# SCH_Amiga-KickSmash-32-in-system-flash_2.net
KiCad netlist of a schematic drawn in EasyEDA
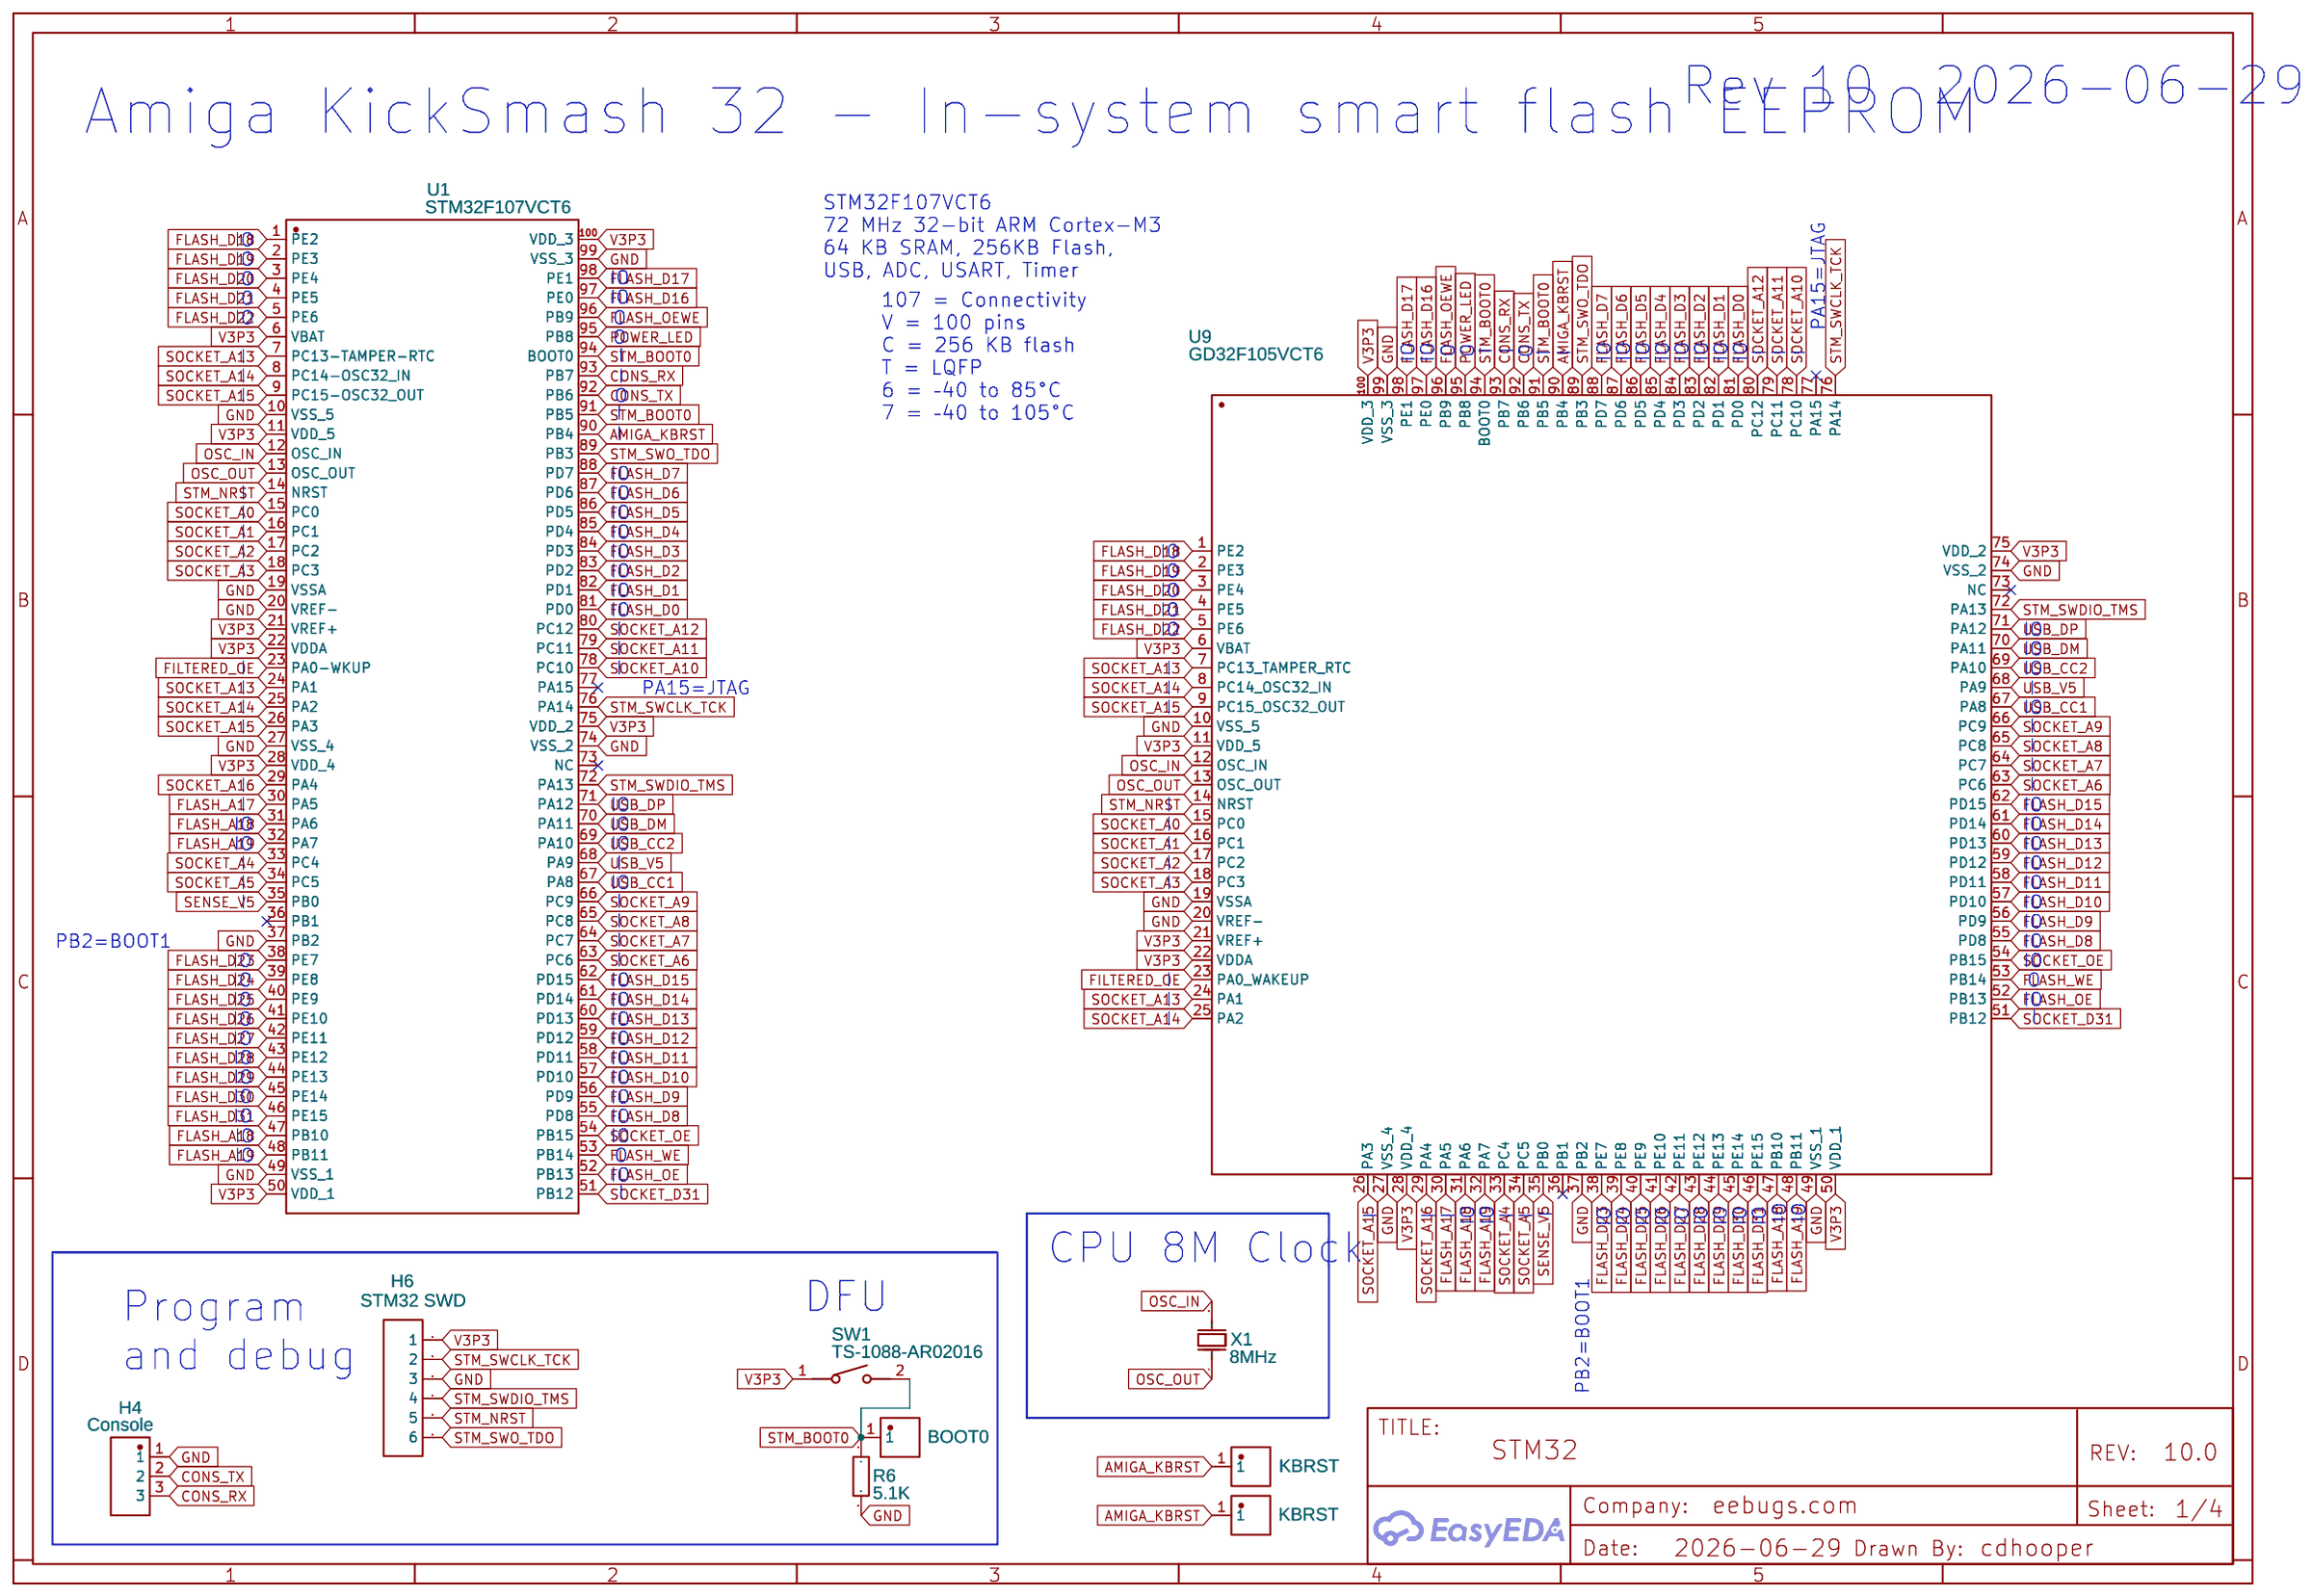
[diagram p0: CPU]
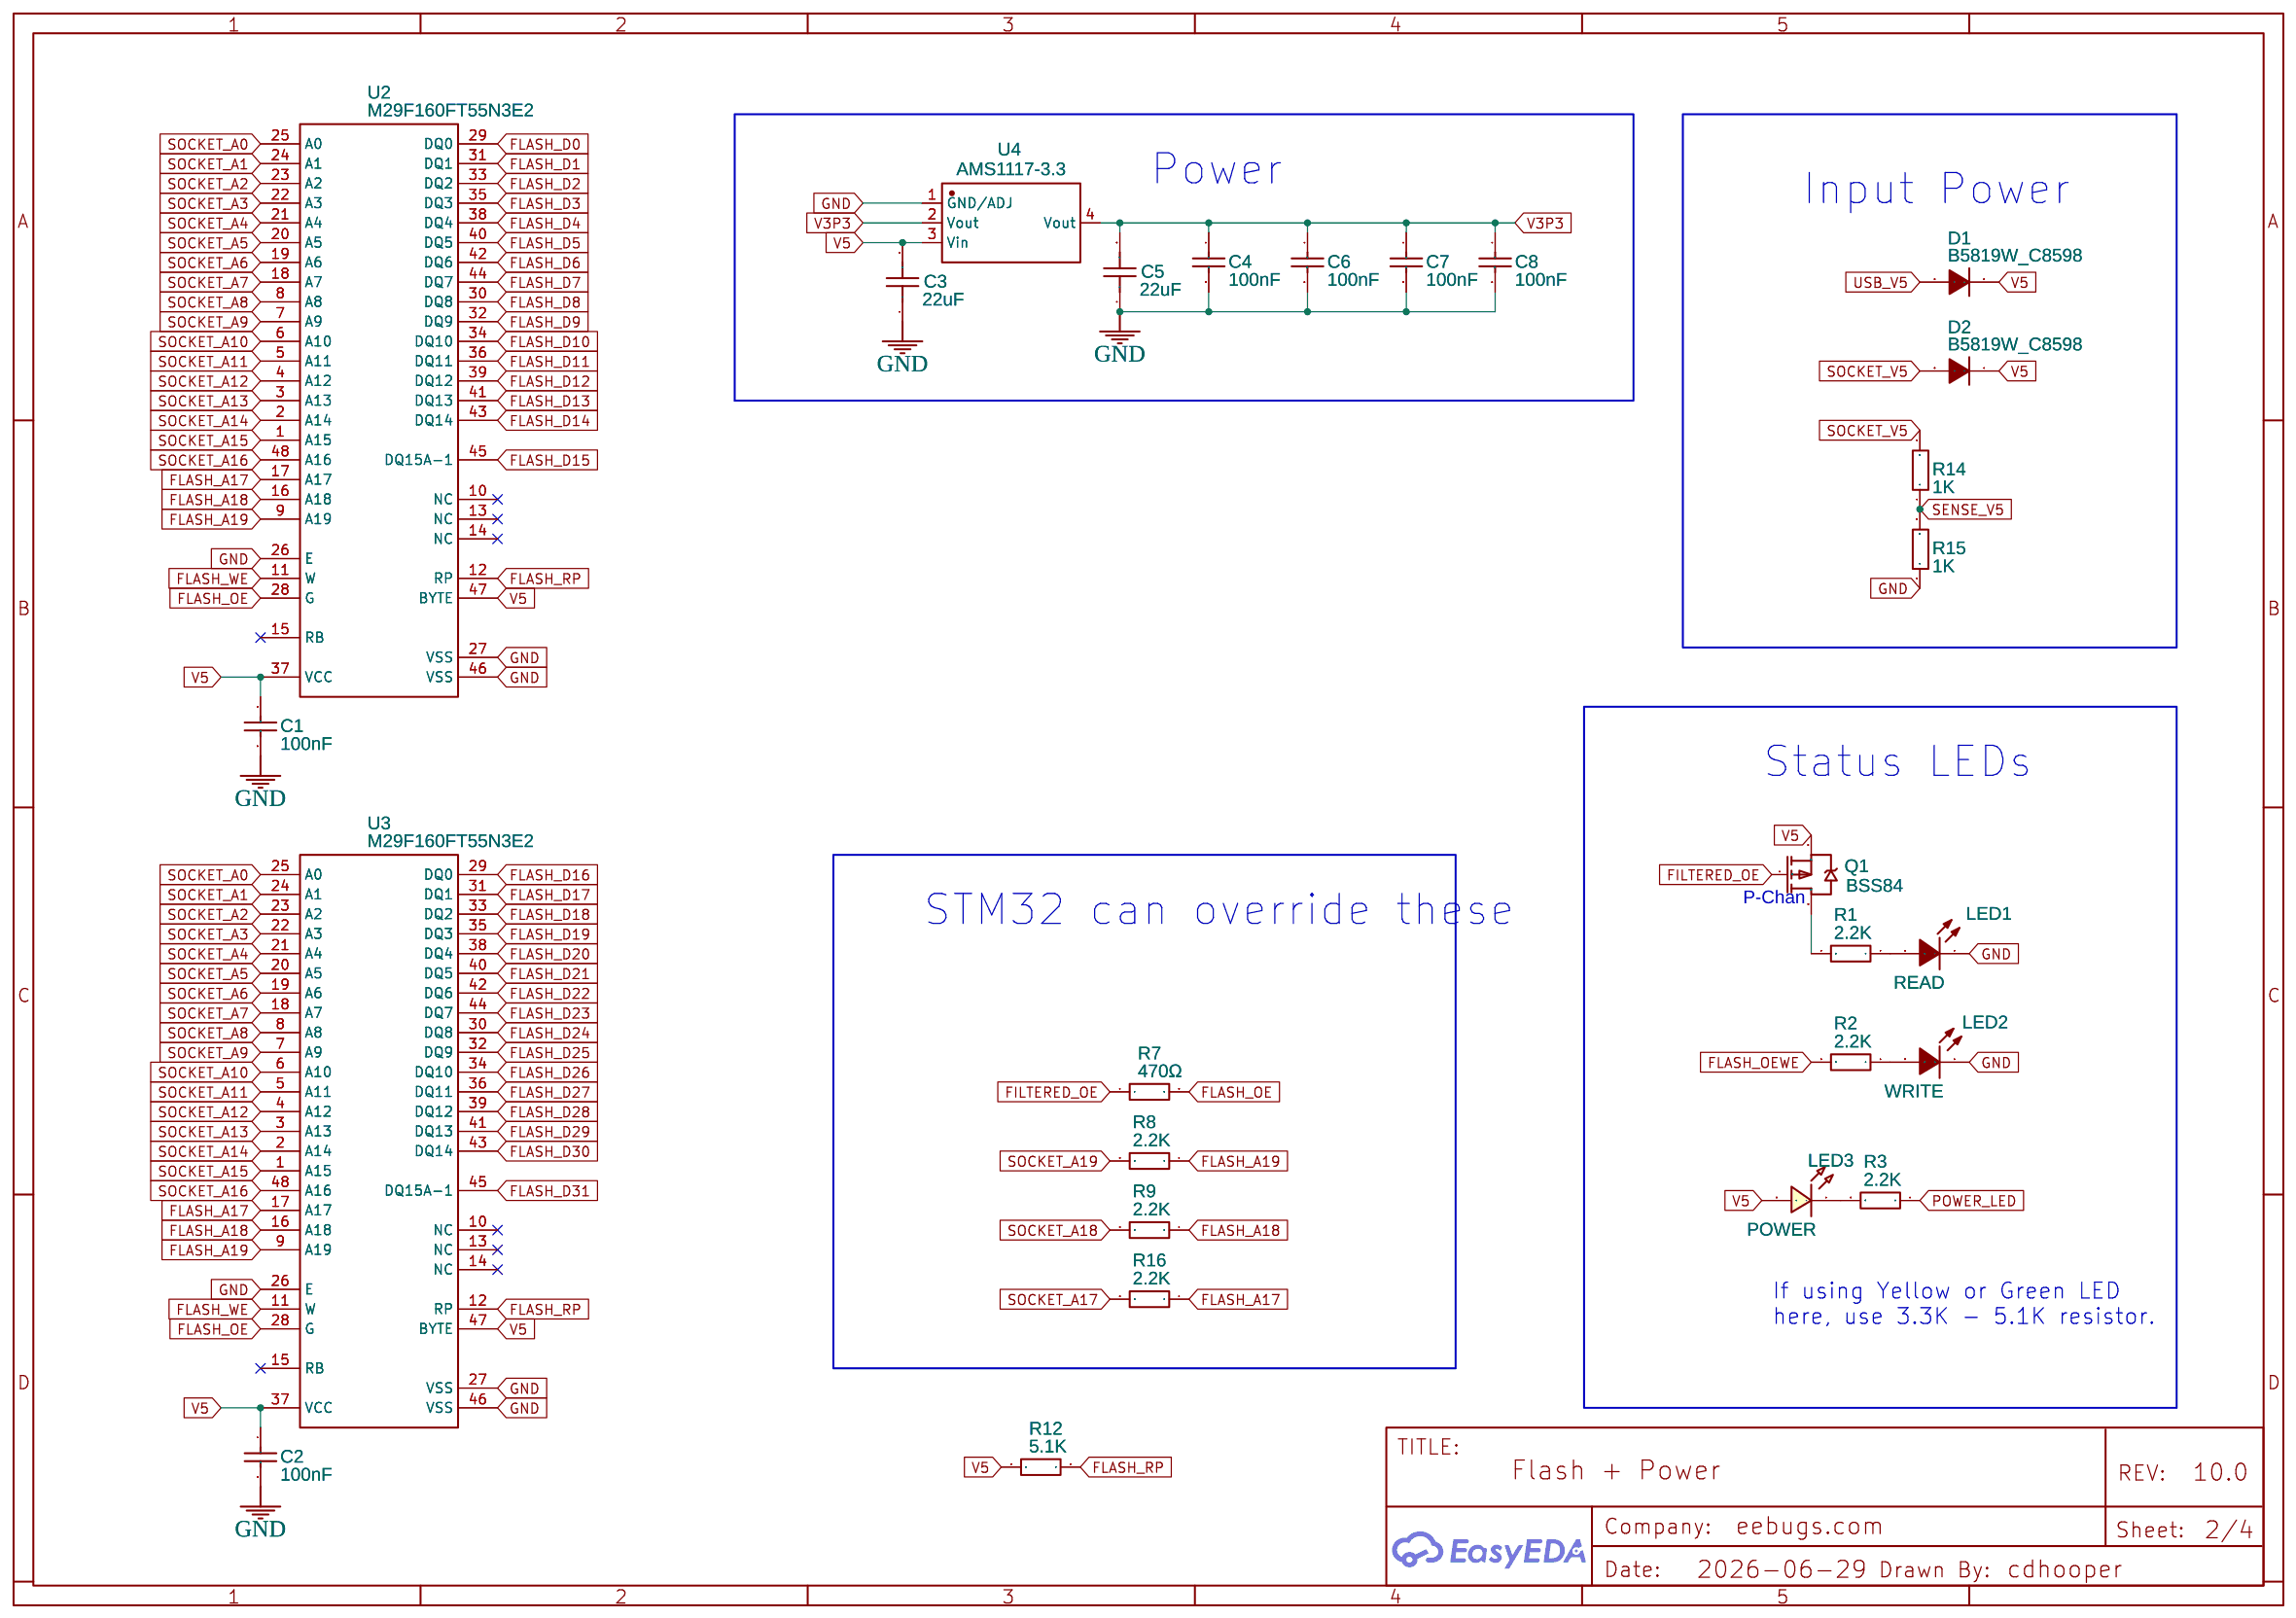
[diagram p1: Flash+PWR]
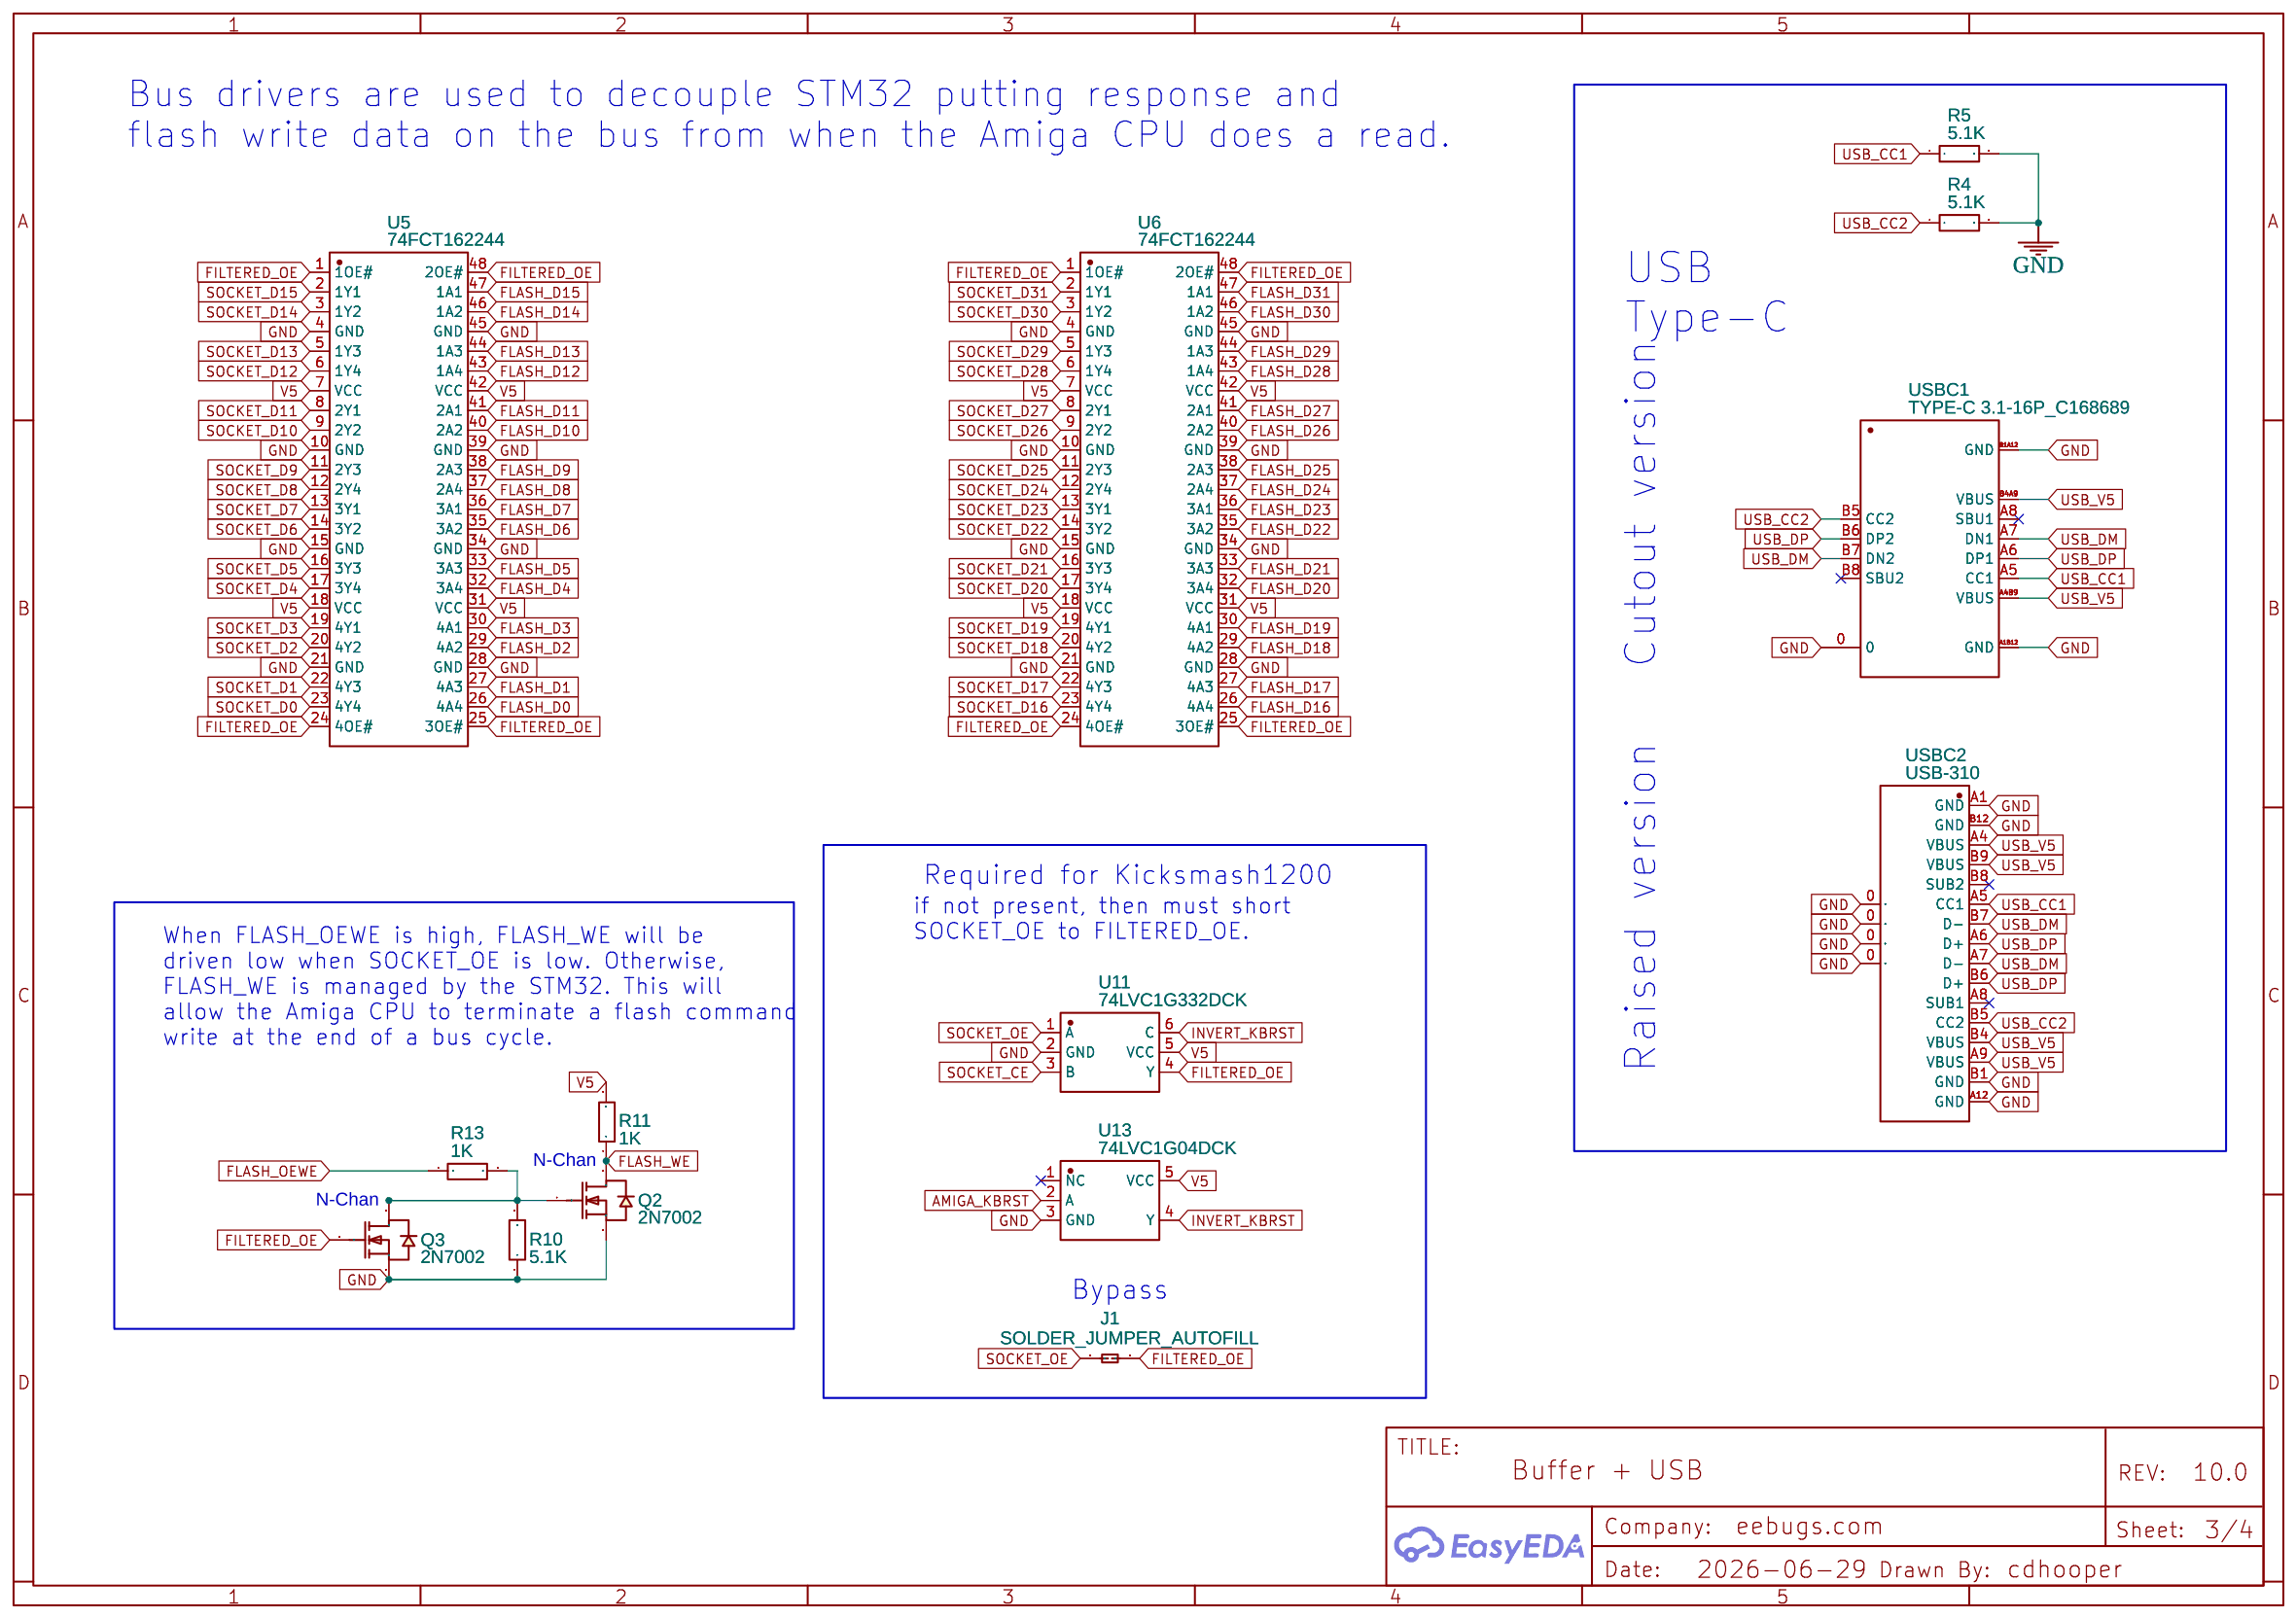
[diagram p2: Buffer+USB]
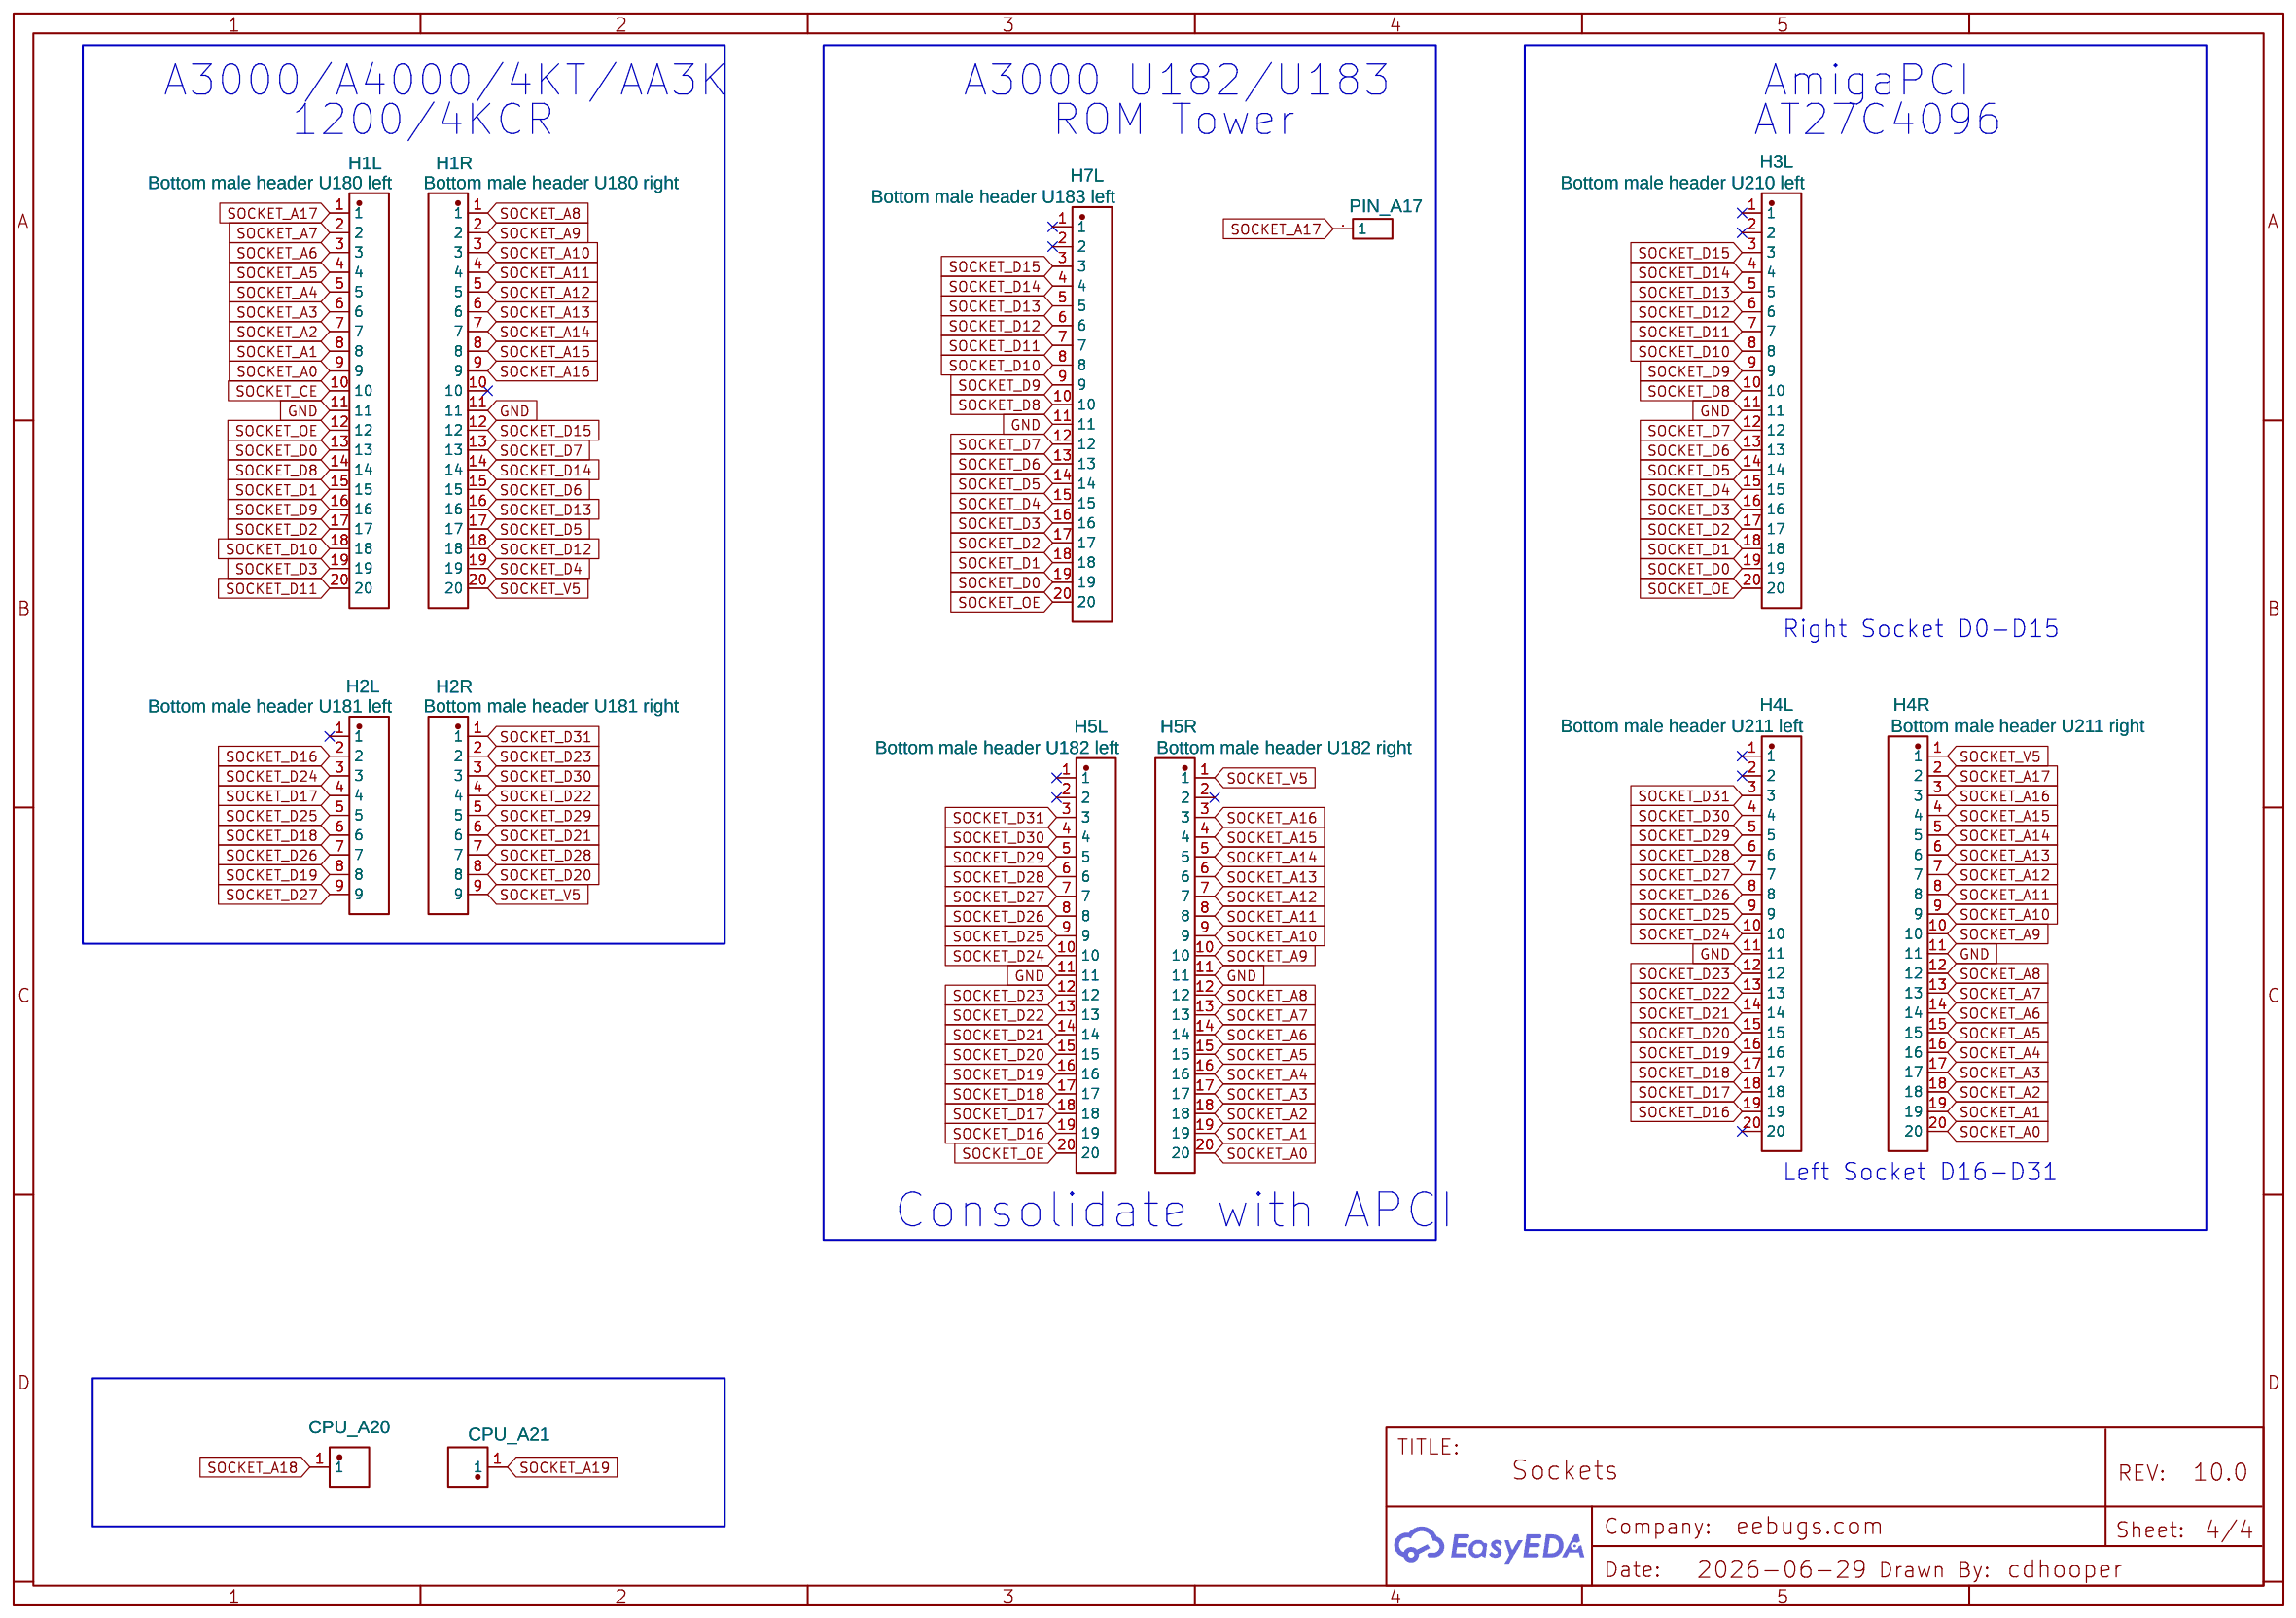
[diagram p3: Sockets]

(export (version "E")
  (design (tool "Eeschema 10.0.6"))
  (components
    (comp (ref "H1")
      (value "KBRST")
      (fields (field (name "Manufacturer Part") "MTAD1-D011196") (field (name "Manufacturer") "MINTRON(明硕)"))
      (libsource (lib "") (part "MTAD1-D011196"))
    )
    (comp (ref "H3")
      (value "KBRST")
      (fields
        (field (name "Manufacturer Part") "X6511WR-01H-C60D30R2")
        (field (name "Manufacturer") "XKB Connection(中国星坤)")
      )
      (libsource (lib "") (part "X6511WR-01H-C30D60R2"))
    )
    (comp (ref "H4")
      (value "Console")
      (fields (field (name "Manufacturer Part") "PZ254R-11-03P") (field (name "Manufacturer") "XFCN(兴飞)"))
      (libsource (lib "") (part "PZ254R-11-03P"))
    )
    (comp (ref "H5")
      (value "BOOT0")
      (fields
        (field (name "Manufacturer Part") "X6511WR-01H-C60D30R2")
        (field (name "Manufacturer") "XKB Connection(中国星坤)")
      )
      (libsource (lib "") (part "X6511WR-01H-C30D60R2"))
    )
    (comp (ref "H6")
      (value "STM32 SWD")
      (fields
        (field (name "Manufacturer Part") "2.54-1*6P反弯排针")
        (field (name "Manufacturer") "BOOMELE(博穆精密)")
      )
      (libsource (lib "") (part "Unknown_205_-100"))
    )
    (comp (ref "R6")
      (value "5.1K")
      (fields (field (name "Manufacturer Part") "0805W8F5101T5E") (field (name "Manufacturer") "UniOhm"))
      (libsource (lib "") (part "0805W8F5101T5E"))
    )
    (comp (ref "SW1")
      (value "TS-1088-AR02016")
      (fields (field (name "Manufacturer") "XUNPU(讯普)"))
      (libsource (lib "") (part "TS-1088-AR02016"))
    )
    (comp (ref "U1")
      (value "STM32F107VCT6")
      (fields (field (name "Manufacturer") "STMicroelectronics"))
      (libsource (lib "") (part "STM32F107VCT6"))
    )
    (comp (ref "U9")
      (value "GD32F105VCT6")
      (fields (field (name "Manufacturer") "GigaDevice(兆易创新)"))
      (libsource (lib "") (part "GD32F105VCT6"))
    )
    (comp (ref "X1")
      (value "8MHz")
      (fields (field (name "Manufacturer Part") "X50328MSB2GI") (field (name "Manufacturer") "YXC"))
      (libsource (lib "") (part "X50328MSB2GI"))
    )
    (comp (ref "C1")
      (value "100nF")
      (fields (field (name "Manufacturer Part") "CC0805KRX7R9BB104") (field (name "Manufacturer") "YAGEO"))
      (libsource (lib "") (part "CC0805KRX7R9BB104"))
    )
    (comp (ref "C2")
      (value "100nF")
      (fields (field (name "Manufacturer Part") "CC0805KRX7R9BB104") (field (name "Manufacturer") "YAGEO"))
      (libsource (lib "") (part "CC0805KRX7R9BB104"))
    )
    (comp (ref "C3")
      (value "22uF")
      (fields (field (name "Manufacturer Part") "CL21A226MAQNNNE") (field (name "Manufacturer") "SAMSUNG"))
      (libsource (lib "") (part "CL21A226MAQNNNE"))
    )
    (comp (ref "C4")
      (value "100nF")
      (fields (field (name "Manufacturer Part") "CC0805KRX7R9BB104") (field (name "Manufacturer") "YAGEO"))
      (libsource (lib "") (part "CC0805KRX7R9BB104"))
    )
    (comp (ref "C5")
      (value "22uF")
      (fields (field (name "Manufacturer Part") "CL21A226MAQNNNE") (field (name "Manufacturer") "SAMSUNG"))
      (libsource (lib "") (part "CL21A226MAQNNNE"))
    )
    (comp (ref "C6")
      (value "100nF")
      (fields (field (name "Manufacturer Part") "CC0805KRX7R9BB104") (field (name "Manufacturer") "YAGEO"))
      (libsource (lib "") (part "CC0805KRX7R9BB104"))
    )
    (comp (ref "C7")
      (value "100nF")
      (fields (field (name "Manufacturer Part") "CC0805KRX7R9BB104") (field (name "Manufacturer") "YAGEO"))
      (libsource (lib "") (part "CC0805KRX7R9BB104"))
    )
    (comp (ref "C8")
      (value "100nF")
      (fields (field (name "Manufacturer Part") "CC0805KRX7R9BB104") (field (name "Manufacturer") "YAGEO"))
      (libsource (lib "") (part "CC0805KRX7R9BB104"))
    )
    (comp (ref "D1")
      (value "B5819W_C8598")
      (fields (field (name "Manufacturer Part") "B5819W") (field (name "Manufacturer") "CJ"))
      (libsource (lib "") (part "B5819W_C8598"))
    )
    (comp (ref "D2")
      (value "B5819W_C8598")
      (fields (field (name "Manufacturer Part") "B5819W") (field (name "Manufacturer") "CJ"))
      (libsource (lib "") (part "B5819W_C8598"))
    )
    (comp (ref "LED1")
      (value "READ")
      (fields (field (name "Manufacturer Part") "17-21SUYC/TR8") (field (name "Manufacturer") "KENTO"))
      (libsource (lib "") (part "17-21SUYC/TR8"))
    )
    (comp (ref "LED2")
      (value "WRITE")
      (fields (field (name "Manufacturer Part") "0805G (Green)") (field (name "Manufacturer") "KENTO"))
      (libsource (lib "") (part "0805G (Green)"))
    )
    (comp (ref "LED3")
      (value "POWER")
      (fields
        (field (name "Manufacturer Part") "P2-0805UVTCS2-0.8T")
        (field (name "Manufacturer") "TUOZHAN(拓展光电)")
      )
      (libsource (lib "") (part "P2-0805UVTCS2-0.8T"))
    )
    (comp (ref "Q1")
      (value "BSS84")
      (fields (field (name "Manufacturer Part") "LBSS84LT1G") (field (name "Manufacturer") "LRC"))
      (libsource (lib "") (part "Unknown_905_-370"))
    )
    (comp (ref "R1")
      (value "2.2K")
      (fields (field (name "Manufacturer Part") "0805W8F2201T5E") (field (name "Manufacturer") "UniOhm"))
      (libsource (lib "") (part "0805W8F2201T5E"))
    )
    (comp (ref "R2")
      (value "2.2K")
      (fields (field (name "Manufacturer Part") "0805W8F2201T5E") (field (name "Manufacturer") "UniOhm"))
      (libsource (lib "") (part "0805W8F2201T5E"))
    )
    (comp (ref "R3")
      (value "2.2K")
      (fields (field (name "Manufacturer Part") "0805W8F2201T5E") (field (name "Manufacturer") "UniOhm"))
      (libsource (lib "") (part "0805W8F2201T5E"))
    )
    (comp (ref "R7")
      (value "470Ω")
      (fields
        (field (name "Manufacturer Part") "0805W8F4700T5E")
        (field (name "Manufacturer") "UNI-ROYAL(厚声)")
      )
      (libsource (lib "") (part "0805W8F4700T5E"))
    )
    (comp (ref "R8")
      (value "2.2K")
      (fields (field (name "Manufacturer Part") "0805W8F2201T5E") (field (name "Manufacturer") "UniOhm"))
      (libsource (lib "") (part "0805W8F2201T5E"))
    )
    (comp (ref "R9")
      (value "2.2K")
      (fields (field (name "Manufacturer Part") "0805W8F2201T5E") (field (name "Manufacturer") "UniOhm"))
      (libsource (lib "") (part "0805W8F2201T5E"))
    )
    (comp (ref "R12")
      (value "5.1K")
      (fields (field (name "Manufacturer Part") "0805W8F5101T5E") (field (name "Manufacturer") "UniOhm"))
      (libsource (lib "") (part "0805W8F5101T5E"))
    )
    (comp (ref "R14")
      (value "1K")
      (fields (field (name "Manufacturer Part") "0805W8F1001T5E") (field (name "Manufacturer") "UniOhm"))
      (libsource (lib "") (part "0805W8F1001T5E"))
    )
    (comp (ref "R15")
      (value "1K")
      (fields (field (name "Manufacturer Part") "0805W8F1001T5E") (field (name "Manufacturer") "UniOhm"))
      (libsource (lib "") (part "0805W8F1001T5E"))
    )
    (comp (ref "R16")
      (value "2.2K")
      (fields (field (name "Manufacturer Part") "0805W8F2201T5E") (field (name "Manufacturer") "UniOhm"))
      (libsource (lib "") (part "0805W8F2201T5E"))
    )
    (comp (ref "U2") (value "M29F160FT55N3E2") (libsource (lib "") (part "M29F160FT55N3E2")))
    (comp (ref "U3") (value "M29F160FT55N3E2") (libsource (lib "") (part "M29F160FT55N3E2")))
    (comp (ref "U4")
      (value "AMS1117-3.3")
      (fields (field (name "Manufacturer") "AMS"))
      (libsource (lib "") (part "AMS1117-3.3"))
    )
    (comp (ref "J1") (value "SOLDER_JUMPER_AUTOFILL") (libsource (lib "") (part "JUMPER_SOLDER_AUTOFILL")))
    (comp (ref "Q2")
      (value "2N7002")
      (fields (field (name "Manufacturer") "CJ(江苏长电/长晶)"))
      (libsource (lib "") (part "AO3400A"))
    )
    (comp (ref "Q3")
      (value "2N7002")
      (fields (field (name "Manufacturer") "CJ(江苏长电/长晶)"))
      (libsource (lib "") (part "AO3400A"))
    )
    (comp (ref "R4")
      (value "5.1K")
      (fields (field (name "Manufacturer Part") "0805W8F5101T5E") (field (name "Manufacturer") "UniOhm"))
      (libsource (lib "") (part "0805W8F5101T5E"))
    )
    (comp (ref "R5")
      (value "5.1K")
      (fields (field (name "Manufacturer Part") "0805W8F5101T5E") (field (name "Manufacturer") "UniOhm"))
      (libsource (lib "") (part "0805W8F5101T5E"))
    )
    (comp (ref "R10")
      (value "5.1K")
      (fields (field (name "Manufacturer Part") "0805W8F5101T5E") (field (name "Manufacturer") "UniOhm"))
      (libsource (lib "") (part "0805W8F5101T5E_1"))
    )
    (comp (ref "R11")
      (value "1K")
      (fields (field (name "Manufacturer Part") "0805W8F1001T5E") (field (name "Manufacturer") "UniOhm"))
      (libsource (lib "") (part "0805W8F1001T5E"))
    )
    (comp (ref "R13")
      (value "1K")
      (fields (field (name "Manufacturer Part") "0805W8F1001T5E") (field (name "Manufacturer") "UniOhm"))
      (libsource (lib "") (part "0805W8F1001T5E_1"))
    )
    (comp (ref "U5")
      (value "74FCT162244")
      (fields
        (field (name "Manufacturer Part") "74FCT162244CTPAG")
        (field (name "Manufacturer") "RENESAS(瑞萨)/IDT")
      )
      (libsource (lib "") (part "74FCT162244CTPAG"))
    )
    (comp (ref "U6")
      (value "74FCT162244")
      (fields
        (field (name "Manufacturer Part") "74FCT162244CTPAG")
        (field (name "Manufacturer") "RENESAS(瑞萨)/IDT")
      )
      (libsource (lib "") (part "74FCT162244CTPAG"))
    )
    (comp (ref "U11")
      (value "74LVC1G332DCK")
      (fields (field (name "Manufacturer Part") "SN74LVC1G332DCKR") (field (name "Manufacturer") "TI(德州仪器)"))
      (libsource (lib "") (part "SN74LVC1G332DCKR"))
    )
    (comp (ref "U13")
      (value "74LVC1G04DCK")
      (fields
        (field (name "Manufacturer Part") "SN74LVC1G04DCKR")
        (field (name "Manufacturer") "TECH PUBLIC(台舟)")
      )
      (libsource (lib "") (part "SN74LVC1G04DCKR_C19829627"))
    )
    (comp (ref "USBC1")
      (value "TYPE-C 3.1-16P_C168689")
      (fields (field (name "Manufacturer") "LCSC"))
      (libsource (lib "") (part "TYPE-C 3.1-16P_C168689"))
    )
    (comp (ref "USBC2")
      (value "USB-310")
      (fields (field (name "Manufacturer Part") "USB-310-B-SU") (field (name "Manufacturer") "HOOYA(皓宇电子)"))
      (libsource (lib "") (part "USB-310"))
    )
    (comp (ref "H1L")
      (value "Bottom male header U180 left")
      (fields (field (name "Manufacturer Part") "PZ254-1-20-Z-C") (field (name "Manufacturer") "HCTL(华灿天禄)"))
      (libsource (lib "") (part "PZ254-1-20-Z-C"))
    )
    (comp (ref "H1R")
      (value "Bottom male header U180 right")
      (fields (field (name "Manufacturer Part") "PZ254-1-20-Z-C") (field (name "Manufacturer") "HCTL(华灿天禄)"))
      (libsource (lib "") (part "PZ254-1-20-Z-C_1"))
    )
    (comp (ref "H2L")
      (value "Bottom male header U181 left")
      (fields (field (name "Manufacturer Part") "PZ254-1-09-Z-C") (field (name "Manufacturer") "HCTL(华灿天禄)"))
      (libsource (lib "") (part "PZ254-1-09-Z-C"))
    )
    (comp (ref "H2R")
      (value "Bottom male header U181 right")
      (fields (field (name "Manufacturer Part") "PZ254-1-09-Z-C") (field (name "Manufacturer") "HCTL(华灿天禄)"))
      (libsource (lib "") (part "PZ254-1-09-Z-C_1"))
    )
    (comp (ref "H3L")
      (value "Bottom male header U210 left")
      (fields (field (name "Manufacturer Part") "2.54mm 1*20PHeader") (field (name "Manufacturer") "BOOMELE"))
      (libsource (lib "") (part "Header-Male-2.54_1x20"))
    )
    (comp (ref "H4L")
      (value "Bottom male header U211 left")
      (fields (field (name "Manufacturer Part") "2.54mm 1*20PHeader") (field (name "Manufacturer") "BOOMELE"))
      (libsource (lib "") (part "Header-Male-2.54_1x20_4"))
    )
    (comp (ref "H4R")
      (value "Bottom male header U211 right")
      (fields (field (name "Manufacturer Part") "2.54mm 1*20PHeader") (field (name "Manufacturer") "BOOMELE"))
      (libsource (lib "") (part "Header-Male-2.54_1x20_3"))
    )
    (comp (ref "H5L")
      (value "Bottom male header U182 left")
      (fields (field (name "Manufacturer Part") "2.54mm 1*20PHeader") (field (name "Manufacturer") "BOOMELE"))
      (libsource (lib "") (part "Header-Male-2.54_1x20_1"))
    )
    (comp (ref "H5R")
      (value "Bottom male header U182 right")
      (fields (field (name "Manufacturer Part") "2.54mm 1*20PHeader") (field (name "Manufacturer") "BOOMELE"))
      (libsource (lib "") (part "Header-Male-2.54_1x20_2"))
    )
    (comp (ref "H7")
      (value "CPU_A20")
      (fields
        (field (name "Manufacturer Part") "X6511WR-01H-C60D30R2")
        (field (name "Manufacturer") "XKB Connection(中国星坤)")
      )
      (libsource (lib "") (part "X6511WR-01H-C30D60R2_1"))
    )
    (comp (ref "H7L")
      (value "Bottom male header U183 left")
      (fields (field (name "Manufacturer Part") "2.54mm 1*20PHeader") (field (name "Manufacturer") "BOOMELE"))
      (libsource (lib "") (part "Header-Male-2.54_1x20_5"))
    )
    (comp (ref "H8")
      (value "CPU_A21")
      (fields
        (field (name "Manufacturer Part") "X6511WR-01H-C60D30R2")
        (field (name "Manufacturer") "XKB Connection(中国星坤)")
      )
      (libsource (lib "") (part "X6511WR-01H-C30D60R2"))
    )
    (comp (ref "H9")
      (value "PIN_A17")
      (fields
        (field (name "Manufacturer Part") "Header-Male-2.54_1x1")
        (field (name "Manufacturer") "ReliaPro")
      )
      (libsource (lib "") (part "Header-Male-2.54_1x1"))
    )
  )
  (nets
    (net (code "1") (name "AMIGA_KBRST") (class "Default")
      (node (ref "H1") (pin "1") (pinfunction "1_1") (pintype "unspecified"))
      (node (ref "H3") (pin "1") (pinfunction "1_1") (pintype "unspecified"))
      (node (ref "U1") (pin "90") (pinfunction "PB4_90") (pintype "unspecified"))
      (node (ref "U13") (pin "2") (pinfunction "A_2") (pintype "unspecified"))
      (node (ref "U9") (pin "90") (pinfunction "PB4_90") (pintype "unspecified"))
    )
    (net (code "2") (name "CONS_RX") (class "Default")
      (node (ref "H4") (pin "3") (pinfunction "3_3") (pintype "unspecified"))
      (node (ref "U1") (pin "93") (pinfunction "PB7_93") (pintype "unspecified"))
      (node (ref "U9") (pin "93") (pinfunction "PB7_93") (pintype "unspecified"))
    )
    (net (code "3") (name "CONS_TX") (class "Default")
      (node (ref "H4") (pin "2") (pinfunction "2_2") (pintype "unspecified"))
      (node (ref "U1") (pin "92") (pinfunction "PB6_92") (pintype "unspecified"))
      (node (ref "U9") (pin "92") (pinfunction "PB6_92") (pintype "unspecified"))
    )
    (net (code "4") (name "FILTERED_OE") (class "Default")
      (node (ref "J1") (pin "2") (pinfunction "2_2") (pintype "unspecified"))
      (node (ref "Q1") (pin "1") (pinfunction "G_1") (pintype "unspecified"))
      (node (ref "Q3") (pin "1") (pinfunction "G_1") (pintype "unspecified"))
      (node (ref "R7") (pin "1") (pinfunction "1_1") (pintype "input"))
      (node (ref "U1") (pin "23") (pinfunction "PA0-WKUP_23") (pintype "unspecified"))
      (node (ref "U11") (pin "4") (pinfunction "Y_4") (pintype "unspecified"))
      (node (ref "U5") (pin "1") (pinfunction "1OE#_1") (pintype "unspecified"))
      (node (ref "U5") (pin "24") (pinfunction "4OE#_24") (pintype "unspecified"))
      (node (ref "U5") (pin "25") (pinfunction "3OE#_25") (pintype "unspecified"))
      (node (ref "U5") (pin "48") (pinfunction "2OE#_48") (pintype "unspecified"))
      (node (ref "U6") (pin "1") (pinfunction "1OE#_1") (pintype "unspecified"))
      (node (ref "U6") (pin "24") (pinfunction "4OE#_24") (pintype "unspecified"))
      (node (ref "U6") (pin "25") (pinfunction "3OE#_25") (pintype "unspecified"))
      (node (ref "U6") (pin "48") (pinfunction "2OE#_48") (pintype "unspecified"))
      (node (ref "U9") (pin "23") (pinfunction "PA0_WAKEUP_23") (pintype "unspecified"))
    )
    (net (code "5") (name "FLASH_A17") (class "Default")
      (node (ref "R16") (pin "1") (pinfunction "1_1") (pintype "input"))
      (node (ref "U1") (pin "30") (pinfunction "PA5_30") (pintype "unspecified"))
      (node (ref "U2") (pin "17") (pinfunction "A17_17") (pintype "unspecified"))
      (node (ref "U3") (pin "17") (pinfunction "A17_17") (pintype "unspecified"))
      (node (ref "U9") (pin "30") (pinfunction "PA5_30") (pintype "unspecified"))
    )
    (net (code "6") (name "FLASH_A18") (class "Default")
      (node (ref "R9") (pin "1") (pinfunction "1_1") (pintype "input"))
      (node (ref "U1") (pin "31") (pinfunction "PA6_31") (pintype "unspecified"))
      (node (ref "U1") (pin "47") (pinfunction "PB10_47") (pintype "unspecified"))
      (node (ref "U2") (pin "16") (pinfunction "A18_16") (pintype "unspecified"))
      (node (ref "U3") (pin "16") (pinfunction "A18_16") (pintype "unspecified"))
      (node (ref "U9") (pin "31") (pinfunction "PA6_31") (pintype "unspecified"))
      (node (ref "U9") (pin "47") (pinfunction "PB10_47") (pintype "unspecified"))
    )
    (net (code "7") (name "FLASH_A19") (class "Default")
      (node (ref "R8") (pin "1") (pinfunction "1_1") (pintype "input"))
      (node (ref "U1") (pin "32") (pinfunction "PA7_32") (pintype "unspecified"))
      (node (ref "U1") (pin "48") (pinfunction "PB11_48") (pintype "unspecified"))
      (node (ref "U2") (pin "9") (pinfunction "A19_9") (pintype "unspecified"))
      (node (ref "U3") (pin "9") (pinfunction "A19_9") (pintype "unspecified"))
      (node (ref "U9") (pin "32") (pinfunction "PA7_32") (pintype "unspecified"))
      (node (ref "U9") (pin "48") (pinfunction "PB11_48") (pintype "unspecified"))
    )
    (net (code "8") (name "FLASH_D0") (class "Default")
      (node (ref "U1") (pin "81") (pinfunction "PD0_81") (pintype "unspecified"))
      (node (ref "U2") (pin "29") (pinfunction "DQ0_29") (pintype "bidirectional"))
      (node (ref "U5") (pin "26") (pinfunction "4A4_26") (pintype "unspecified"))
      (node (ref "U9") (pin "81") (pinfunction "PD0_81") (pintype "unspecified"))
    )
    (net (code "9") (name "FLASH_D1") (class "Default")
      (node (ref "U1") (pin "82") (pinfunction "PD1_82") (pintype "unspecified"))
      (node (ref "U2") (pin "31") (pinfunction "DQ1_31") (pintype "bidirectional"))
      (node (ref "U5") (pin "27") (pinfunction "4A3_27") (pintype "unspecified"))
      (node (ref "U9") (pin "82") (pinfunction "PD1_82") (pintype "unspecified"))
    )
    (net (code "10") (name "FLASH_D2") (class "Default")
      (node (ref "U1") (pin "83") (pinfunction "PD2_83") (pintype "unspecified"))
      (node (ref "U2") (pin "33") (pinfunction "DQ2_33") (pintype "bidirectional"))
      (node (ref "U5") (pin "29") (pinfunction "4A2_29") (pintype "unspecified"))
      (node (ref "U9") (pin "83") (pinfunction "PD2_83") (pintype "unspecified"))
    )
    (net (code "11") (name "FLASH_D3") (class "Default")
      (node (ref "U1") (pin "84") (pinfunction "PD3_84") (pintype "unspecified"))
      (node (ref "U2") (pin "35") (pinfunction "DQ3_35") (pintype "bidirectional"))
      (node (ref "U5") (pin "30") (pinfunction "4A1_30") (pintype "unspecified"))
      (node (ref "U9") (pin "84") (pinfunction "PD3_84") (pintype "unspecified"))
    )
    (net (code "12") (name "FLASH_D4") (class "Default")
      (node (ref "U1") (pin "85") (pinfunction "PD4_85") (pintype "unspecified"))
      (node (ref "U2") (pin "38") (pinfunction "DQ4_38") (pintype "bidirectional"))
      (node (ref "U5") (pin "32") (pinfunction "3A4_32") (pintype "unspecified"))
      (node (ref "U9") (pin "85") (pinfunction "PD4_85") (pintype "unspecified"))
    )
    (net (code "13") (name "FLASH_D5") (class "Default")
      (node (ref "U1") (pin "86") (pinfunction "PD5_86") (pintype "unspecified"))
      (node (ref "U2") (pin "40") (pinfunction "DQ5_40") (pintype "bidirectional"))
      (node (ref "U5") (pin "33") (pinfunction "3A3_33") (pintype "unspecified"))
      (node (ref "U9") (pin "86") (pinfunction "PD5_86") (pintype "unspecified"))
    )
    (net (code "14") (name "FLASH_D6") (class "Default")
      (node (ref "U1") (pin "87") (pinfunction "PD6_87") (pintype "unspecified"))
      (node (ref "U2") (pin "42") (pinfunction "DQ6_42") (pintype "bidirectional"))
      (node (ref "U5") (pin "35") (pinfunction "3A2_35") (pintype "unspecified"))
      (node (ref "U9") (pin "87") (pinfunction "PD6_87") (pintype "unspecified"))
    )
    (net (code "15") (name "FLASH_D7") (class "Default")
      (node (ref "U1") (pin "88") (pinfunction "PD7_88") (pintype "unspecified"))
      (node (ref "U2") (pin "44") (pinfunction "DQ7_44") (pintype "bidirectional"))
      (node (ref "U5") (pin "36") (pinfunction "3A1_36") (pintype "unspecified"))
      (node (ref "U9") (pin "88") (pinfunction "PD7_88") (pintype "unspecified"))
    )
    (net (code "16") (name "FLASH_D8") (class "Default")
      (node (ref "U1") (pin "55") (pinfunction "PD8_55") (pintype "unspecified"))
      (node (ref "U2") (pin "30") (pinfunction "DQ8_30") (pintype "bidirectional"))
      (node (ref "U5") (pin "37") (pinfunction "2A4_37") (pintype "unspecified"))
      (node (ref "U9") (pin "55") (pinfunction "PD8_55") (pintype "unspecified"))
    )
    (net (code "17") (name "FLASH_D9") (class "Default")
      (node (ref "U1") (pin "56") (pinfunction "PD9_56") (pintype "unspecified"))
      (node (ref "U2") (pin "32") (pinfunction "DQ9_32") (pintype "bidirectional"))
      (node (ref "U5") (pin "38") (pinfunction "2A3_38") (pintype "unspecified"))
      (node (ref "U9") (pin "56") (pinfunction "PD9_56") (pintype "unspecified"))
    )
    (net (code "18") (name "FLASH_D10") (class "Default")
      (node (ref "U1") (pin "57") (pinfunction "PD10_57") (pintype "unspecified"))
      (node (ref "U2") (pin "34") (pinfunction "DQ10_34") (pintype "bidirectional"))
      (node (ref "U5") (pin "40") (pinfunction "2A2_40") (pintype "unspecified"))
      (node (ref "U9") (pin "57") (pinfunction "PD10_57") (pintype "unspecified"))
    )
    (net (code "19") (name "FLASH_D11") (class "Default")
      (node (ref "U1") (pin "58") (pinfunction "PD11_58") (pintype "unspecified"))
      (node (ref "U2") (pin "36") (pinfunction "DQ11_36") (pintype "bidirectional"))
      (node (ref "U5") (pin "41") (pinfunction "2A1_41") (pintype "unspecified"))
      (node (ref "U9") (pin "58") (pinfunction "PD11_58") (pintype "unspecified"))
    )
    (net (code "20") (name "FLASH_D12") (class "Default")
      (node (ref "U1") (pin "59") (pinfunction "PD12_59") (pintype "unspecified"))
      (node (ref "U2") (pin "39") (pinfunction "DQ12_39") (pintype "bidirectional"))
      (node (ref "U5") (pin "43") (pinfunction "1A4_43") (pintype "unspecified"))
      (node (ref "U9") (pin "59") (pinfunction "PD12_59") (pintype "unspecified"))
    )
    (net (code "21") (name "FLASH_D13") (class "Default")
      (node (ref "U1") (pin "60") (pinfunction "PD13_60") (pintype "unspecified"))
      (node (ref "U2") (pin "41") (pinfunction "DQ13_41") (pintype "bidirectional"))
      (node (ref "U5") (pin "44") (pinfunction "1A3_44") (pintype "unspecified"))
      (node (ref "U9") (pin "60") (pinfunction "PD13_60") (pintype "unspecified"))
    )
    (net (code "22") (name "FLASH_D14") (class "Default")
      (node (ref "U1") (pin "61") (pinfunction "PD14_61") (pintype "unspecified"))
      (node (ref "U2") (pin "43") (pinfunction "DQ14_43") (pintype "bidirectional"))
      (node (ref "U5") (pin "46") (pinfunction "1A2_46") (pintype "unspecified"))
      (node (ref "U9") (pin "61") (pinfunction "PD14_61") (pintype "unspecified"))
    )
    (net (code "23") (name "FLASH_D15") (class "Default")
      (node (ref "U1") (pin "62") (pinfunction "PD15_62") (pintype "unspecified"))
      (node (ref "U2") (pin "45") (pinfunction "DQ15A-1_45") (pintype "bidirectional"))
      (node (ref "U5") (pin "47") (pinfunction "1A1_47") (pintype "unspecified"))
      (node (ref "U9") (pin "62") (pinfunction "PD15_62") (pintype "unspecified"))
    )
    (net (code "24") (name "FLASH_D16") (class "Default")
      (node (ref "U1") (pin "97") (pinfunction "PE0_97") (pintype "unspecified"))
      (node (ref "U3") (pin "29") (pinfunction "DQ0_29") (pintype "bidirectional"))
      (node (ref "U6") (pin "26") (pinfunction "4A4_26") (pintype "unspecified"))
      (node (ref "U9") (pin "97") (pinfunction "PE0_97") (pintype "unspecified"))
    )
    (net (code "25") (name "FLASH_D17") (class "Default")
      (node (ref "U1") (pin "98") (pinfunction "PE1_98") (pintype "unspecified"))
      (node (ref "U3") (pin "31") (pinfunction "DQ1_31") (pintype "bidirectional"))
      (node (ref "U6") (pin "27") (pinfunction "4A3_27") (pintype "unspecified"))
      (node (ref "U9") (pin "98") (pinfunction "PE1_98") (pintype "unspecified"))
    )
    (net (code "26") (name "FLASH_D18") (class "Default")
      (node (ref "U1") (pin "1") (pinfunction "PE2_1") (pintype "unspecified"))
      (node (ref "U3") (pin "33") (pinfunction "DQ2_33") (pintype "bidirectional"))
      (node (ref "U6") (pin "29") (pinfunction "4A2_29") (pintype "unspecified"))
      (node (ref "U9") (pin "1") (pinfunction "PE2_1") (pintype "unspecified"))
    )
    (net (code "27") (name "FLASH_D19") (class "Default")
      (node (ref "U1") (pin "2") (pinfunction "PE3_2") (pintype "unspecified"))
      (node (ref "U3") (pin "35") (pinfunction "DQ3_35") (pintype "bidirectional"))
      (node (ref "U6") (pin "30") (pinfunction "4A1_30") (pintype "unspecified"))
      (node (ref "U9") (pin "2") (pinfunction "PE3_2") (pintype "unspecified"))
    )
    (net (code "28") (name "FLASH_D20") (class "Default")
      (node (ref "U1") (pin "3") (pinfunction "PE4_3") (pintype "unspecified"))
      (node (ref "U3") (pin "38") (pinfunction "DQ4_38") (pintype "bidirectional"))
      (node (ref "U6") (pin "32") (pinfunction "3A4_32") (pintype "unspecified"))
      (node (ref "U9") (pin "3") (pinfunction "PE4_3") (pintype "unspecified"))
    )
    (net (code "29") (name "FLASH_D21") (class "Default")
      (node (ref "U1") (pin "4") (pinfunction "PE5_4") (pintype "unspecified"))
      (node (ref "U3") (pin "40") (pinfunction "DQ5_40") (pintype "bidirectional"))
      (node (ref "U6") (pin "33") (pinfunction "3A3_33") (pintype "unspecified"))
      (node (ref "U9") (pin "4") (pinfunction "PE5_4") (pintype "unspecified"))
    )
    (net (code "30") (name "FLASH_D22") (class "Default")
      (node (ref "U1") (pin "5") (pinfunction "PE6_5") (pintype "unspecified"))
      (node (ref "U3") (pin "42") (pinfunction "DQ6_42") (pintype "bidirectional"))
      (node (ref "U6") (pin "35") (pinfunction "3A2_35") (pintype "unspecified"))
      (node (ref "U9") (pin "5") (pinfunction "PE6_5") (pintype "unspecified"))
    )
    (net (code "31") (name "FLASH_D23") (class "Default")
      (node (ref "U1") (pin "38") (pinfunction "PE7_38") (pintype "unspecified"))
      (node (ref "U3") (pin "44") (pinfunction "DQ7_44") (pintype "bidirectional"))
      (node (ref "U6") (pin "36") (pinfunction "3A1_36") (pintype "unspecified"))
      (node (ref "U9") (pin "38") (pinfunction "PE7_38") (pintype "unspecified"))
    )
    (net (code "32") (name "FLASH_D24") (class "Default")
      (node (ref "U1") (pin "39") (pinfunction "PE8_39") (pintype "unspecified"))
      (node (ref "U3") (pin "30") (pinfunction "DQ8_30") (pintype "bidirectional"))
      (node (ref "U6") (pin "37") (pinfunction "2A4_37") (pintype "unspecified"))
      (node (ref "U9") (pin "39") (pinfunction "PE8_39") (pintype "unspecified"))
    )
    (net (code "33") (name "FLASH_D25") (class "Default")
      (node (ref "U1") (pin "40") (pinfunction "PE9_40") (pintype "unspecified"))
      (node (ref "U3") (pin "32") (pinfunction "DQ9_32") (pintype "bidirectional"))
      (node (ref "U6") (pin "38") (pinfunction "2A3_38") (pintype "unspecified"))
      (node (ref "U9") (pin "40") (pinfunction "PE9_40") (pintype "unspecified"))
    )
    (net (code "34") (name "FLASH_D26") (class "Default")
      (node (ref "U1") (pin "41") (pinfunction "PE10_41") (pintype "unspecified"))
      (node (ref "U3") (pin "34") (pinfunction "DQ10_34") (pintype "bidirectional"))
      (node (ref "U6") (pin "40") (pinfunction "2A2_40") (pintype "unspecified"))
      (node (ref "U9") (pin "41") (pinfunction "PE10_41") (pintype "unspecified"))
    )
    (net (code "35") (name "FLASH_D27") (class "Default")
      (node (ref "U1") (pin "42") (pinfunction "PE11_42") (pintype "unspecified"))
      (node (ref "U3") (pin "36") (pinfunction "DQ11_36") (pintype "bidirectional"))
      (node (ref "U6") (pin "41") (pinfunction "2A1_41") (pintype "unspecified"))
      (node (ref "U9") (pin "42") (pinfunction "PE11_42") (pintype "unspecified"))
    )
    (net (code "36") (name "FLASH_D28") (class "Default")
      (node (ref "U1") (pin "43") (pinfunction "PE12_43") (pintype "unspecified"))
      (node (ref "U3") (pin "39") (pinfunction "DQ12_39") (pintype "bidirectional"))
      (node (ref "U6") (pin "43") (pinfunction "1A4_43") (pintype "unspecified"))
      (node (ref "U9") (pin "43") (pinfunction "PE12_43") (pintype "unspecified"))
    )
    (net (code "37") (name "FLASH_D29") (class "Default")
      (node (ref "U1") (pin "44") (pinfunction "PE13_44") (pintype "unspecified"))
      (node (ref "U3") (pin "41") (pinfunction "DQ13_41") (pintype "bidirectional"))
      (node (ref "U6") (pin "44") (pinfunction "1A3_44") (pintype "unspecified"))
      (node (ref "U9") (pin "44") (pinfunction "PE13_44") (pintype "unspecified"))
    )
    (net (code "38") (name "FLASH_D30") (class "Default")
      (node (ref "U1") (pin "45") (pinfunction "PE14_45") (pintype "unspecified"))
      (node (ref "U3") (pin "43") (pinfunction "DQ14_43") (pintype "bidirectional"))
      (node (ref "U6") (pin "46") (pinfunction "1A2_46") (pintype "unspecified"))
      (node (ref "U9") (pin "45") (pinfunction "PE14_45") (pintype "unspecified"))
    )
    (net (code "39") (name "FLASH_D31") (class "Default")
      (node (ref "U1") (pin "46") (pinfunction "PE15_46") (pintype "unspecified"))
      (node (ref "U3") (pin "45") (pinfunction "DQ15A-1_45") (pintype "bidirectional"))
      (node (ref "U6") (pin "47") (pinfunction "1A1_47") (pintype "unspecified"))
      (node (ref "U9") (pin "46") (pinfunction "PE15_46") (pintype "unspecified"))
    )
    (net (code "40") (name "FLASH_OE") (class "Default")
      (node (ref "R7") (pin "2") (pinfunction "2_2") (pintype "input"))
      (node (ref "U1") (pin "52") (pinfunction "PB13_52") (pintype "unspecified"))
      (node (ref "U2") (pin "28") (pinfunction "G_28") (pintype "unspecified"))
      (node (ref "U3") (pin "28") (pinfunction "G_28") (pintype "unspecified"))
      (node (ref "U9") (pin "52") (pinfunction "PB13_52") (pintype "unspecified"))
    )
    (net (code "41") (name "FLASH_OEWE") (class "Default")
      (node (ref "R13") (pin "1") (pinfunction "1_1") (pintype "input"))
      (node (ref "R2") (pin "2") (pinfunction "2_2") (pintype "input"))
      (node (ref "U1") (pin "96") (pinfunction "PB9_96") (pintype "unspecified"))
      (node (ref "U9") (pin "96") (pinfunction "PB9_96") (pintype "unspecified"))
    )
    (net (code "42") (name "FLASH_RP") (class "Default")
      (node (ref "R12") (pin "2") (pinfunction "2_2") (pintype "input"))
      (node (ref "U2") (pin "12") (pinfunction "RP_12") (pintype "unspecified"))
      (node (ref "U3") (pin "12") (pinfunction "RP_12") (pintype "unspecified"))
    )
    (net (code "43") (name "FLASH_WE") (class "Default")
      (node (ref "Q2") (pin "3") (pinfunction "D_3") (pintype "unspecified"))
      (node (ref "R11") (pin "1") (pinfunction "1_1") (pintype "input"))
      (node (ref "U1") (pin "53") (pinfunction "PB14_53") (pintype "unspecified"))
      (node (ref "U2") (pin "11") (pinfunction "W_11") (pintype "unspecified"))
      (node (ref "U3") (pin "11") (pinfunction "W_11") (pintype "unspecified"))
      (node (ref "U9") (pin "53") (pinfunction "PB14_53") (pintype "unspecified"))
    )
    (net (code "44") (name "GND") (class "Default")
      (node (ref "C1") (pin "2") (pinfunction "2_2") (pintype "input"))
      (node (ref "C2") (pin "2") (pinfunction "2_2") (pintype "input"))
      (node (ref "C3") (pin "1") (pinfunction "1_1") (pintype "unspecified"))
      (node (ref "C4") (pin "2") (pinfunction "2_2") (pintype "input"))
      (node (ref "C5") (pin "1") (pinfunction "1_1") (pintype "unspecified"))
      (node (ref "C6") (pin "2") (pinfunction "2_2") (pintype "input"))
      (node (ref "C7") (pin "2") (pinfunction "2_2") (pintype "input"))
      (node (ref "C8") (pin "2") (pinfunction "2_2") (pintype "input"))
      (node (ref "H1L") (pin "11") (pinfunction "11_11") (pintype "unspecified"))
      (node (ref "H1R") (pin "11") (pinfunction "11_11") (pintype "unspecified"))
      (node (ref "H3L") (pin "11") (pinfunction "11_11") (pintype "unspecified"))
      (node (ref "H4") (pin "1") (pinfunction "1_1") (pintype "unspecified"))
      (node (ref "H4L") (pin "11") (pinfunction "11_11") (pintype "unspecified"))
      (node (ref "H4R") (pin "11") (pinfunction "11_11") (pintype "unspecified"))
      (node (ref "H5L") (pin "11") (pinfunction "11_11") (pintype "unspecified"))
      (node (ref "H5R") (pin "11") (pinfunction "11_11") (pintype "unspecified"))
      (node (ref "H6") (pin "3") (pinfunction "3_3") (pintype "input"))
      (node (ref "H7L") (pin "11") (pinfunction "11_11") (pintype "unspecified"))
      (node (ref "LED1") (pin "1") (pinfunction "-_1") (pintype "unspecified"))
      (node (ref "LED2") (pin "1") (pinfunction "K_1") (pintype "unspecified"))
      (node (ref "Q2") (pin "2") (pinfunction "S_2") (pintype "unspecified"))
      (node (ref "Q3") (pin "2") (pinfunction "S_2") (pintype "unspecified"))
      (node (ref "R10") (pin "1") (pinfunction "1_1") (pintype "input"))
      (node (ref "R15") (pin "1") (pinfunction "1_1") (pintype "input"))
      (node (ref "R4") (pin "2") (pinfunction "2_2") (pintype "input"))
      (node (ref "R5") (pin "2") (pinfunction "2_2") (pintype "input"))
      (node (ref "R6") (pin "2") (pinfunction "2_2") (pintype "input"))
      (node (ref "U1") (pin "10") (pinfunction "VSS_5_10") (pintype "unspecified"))
      (node (ref "U1") (pin "19") (pinfunction "VSSA_19") (pintype "unspecified"))
      (node (ref "U1") (pin "20") (pinfunction "VREF-_20") (pintype "unspecified"))
      (node (ref "U1") (pin "27") (pinfunction "VSS_4_27") (pintype "unspecified"))
      (node (ref "U1") (pin "37") (pinfunction "PB2_37") (pintype "unspecified"))
      (node (ref "U1") (pin "49") (pinfunction "VSS_1_49") (pintype "unspecified"))
      (node (ref "U1") (pin "74") (pinfunction "VSS_2_74") (pintype "unspecified"))
      (node (ref "U1") (pin "99") (pinfunction "VSS_3_99") (pintype "unspecified"))
      (node (ref "U11") (pin "2") (pinfunction "GND_2") (pintype "unspecified"))
      (node (ref "U13") (pin "3") (pinfunction "GND_3") (pintype "unspecified"))
      (node (ref "U2") (pin "26") (pinfunction "E_26") (pintype "unspecified"))
      (node (ref "U2") (pin "27") (pinfunction "VSS_27") (pintype "passive"))
      (node (ref "U2") (pin "46") (pinfunction "VSS_46") (pintype "passive"))
      (node (ref "U3") (pin "26") (pinfunction "E_26") (pintype "unspecified"))
      (node (ref "U3") (pin "27") (pinfunction "VSS_27") (pintype "passive"))
      (node (ref "U3") (pin "46") (pinfunction "VSS_46") (pintype "passive"))
      (node (ref "U4") (pin "1") (pinfunction "GND/ADJ_1") (pintype "unspecified"))
      (node (ref "U5") (pin "10") (pinfunction "GND_10") (pintype "unspecified"))
      (node (ref "U5") (pin "15") (pinfunction "GND_15") (pintype "unspecified"))
      (node (ref "U5") (pin "21") (pinfunction "GND_21") (pintype "unspecified"))
      (node (ref "U5") (pin "28") (pinfunction "GND_28") (pintype "unspecified"))
      (node (ref "U5") (pin "34") (pinfunction "GND_34") (pintype "unspecified"))
      (node (ref "U5") (pin "39") (pinfunction "GND_39") (pintype "unspecified"))
      (node (ref "U5") (pin "4") (pinfunction "GND_4") (pintype "unspecified"))
      (node (ref "U5") (pin "45") (pinfunction "GND_45") (pintype "unspecified"))
      (node (ref "U6") (pin "10") (pinfunction "GND_10") (pintype "unspecified"))
      (node (ref "U6") (pin "15") (pinfunction "GND_15") (pintype "unspecified"))
      (node (ref "U6") (pin "21") (pinfunction "GND_21") (pintype "unspecified"))
      (node (ref "U6") (pin "28") (pinfunction "GND_28") (pintype "unspecified"))
      (node (ref "U6") (pin "34") (pinfunction "GND_34") (pintype "unspecified"))
      (node (ref "U6") (pin "39") (pinfunction "GND_39") (pintype "unspecified"))
      (node (ref "U6") (pin "4") (pinfunction "GND_4") (pintype "unspecified"))
      (node (ref "U6") (pin "45") (pinfunction "GND_45") (pintype "unspecified"))
      (node (ref "U9") (pin "10") (pinfunction "VSS_5_10") (pintype "unspecified"))
      (node (ref "U9") (pin "19") (pinfunction "VSSA_19") (pintype "unspecified"))
      (node (ref "U9") (pin "20") (pinfunction "VREF-_20") (pintype "unspecified"))
      (node (ref "U9") (pin "27") (pinfunction "VSS_4_27") (pintype "unspecified"))
      (node (ref "U9") (pin "37") (pinfunction "PB2_37") (pintype "unspecified"))
      (node (ref "U9") (pin "49") (pinfunction "VSS_1_49") (pintype "unspecified"))
      (node (ref "U9") (pin "74") (pinfunction "VSS_2_74") (pintype "unspecified"))
      (node (ref "U9") (pin "99") (pinfunction "VSS_3_99") (pintype "unspecified"))
      (node (ref "USBC1") (pin "0") (pinfunction "0_0") (pintype "unspecified"))
      (node (ref "USBC1") (pin "A1B12") (pinfunction "GND_A1B12") (pintype "unspecified"))
      (node (ref "USBC1") (pin "B1A12") (pinfunction "GND_B1A12") (pintype "unspecified"))
      (node (ref "USBC2") (pin "0") (pinfunction "0_0") (pintype "unspecified"))
      (node (ref "USBC2") (pin "A1") (pinfunction "GND_A1") (pintype "unspecified"))
      (node (ref "USBC2") (pin "A12") (pinfunction "GND_A12") (pintype "unspecified"))
      (node (ref "USBC2") (pin "B1") (pinfunction "GND_B1") (pintype "unspecified"))
      (node (ref "USBC2") (pin "B12") (pinfunction "GND_B12") (pintype "unspecified"))
    )
    (net (code "45") (name "INVERT_KBRST") (class "Default")
      (node (ref "U11") (pin "6") (pinfunction "C_6") (pintype "unspecified"))
      (node (ref "U13") (pin "4") (pinfunction "Y_4") (pintype "unspecified"))
    )
    (net (code "46") (name "Net-(LED1-+)") (class "Default")
      (node (ref "LED1") (pin "2") (pinfunction "+_2") (pintype "unspecified"))
      (node (ref "R1") (pin "1") (pinfunction "1_1") (pintype "input"))
    )
    (net (code "47") (name "Net-(LED2-A)") (class "Default")
      (node (ref "LED2") (pin "2") (pinfunction "A_2") (pintype "unspecified"))
      (node (ref "R2") (pin "1") (pinfunction "1_1") (pintype "input"))
    )
    (net (code "48") (name "Net-(LED3--)") (class "Default")
      (node (ref "LED3") (pin "1") (pinfunction "-_1") (pintype "unspecified"))
      (node (ref "R3") (pin "2") (pinfunction "2_2") (pintype "input"))
    )
    (net (code "49") (name "Net-(Q1-D)") (class "Default")
      (node (ref "Q1") (pin "3") (pinfunction "D_3") (pintype "unspecified"))
      (node (ref "R1") (pin "2") (pinfunction "2_2") (pintype "input"))
    )
    (net (code "50") (name "Net-(Q2-G)") (class "Default")
      (node (ref "Q2") (pin "1") (pinfunction "G_1") (pintype "unspecified"))
      (node (ref "Q3") (pin "3") (pinfunction "D_3") (pintype "unspecified"))
      (node (ref "R10") (pin "2") (pinfunction "2_2") (pintype "input"))
      (node (ref "R13") (pin "2") (pinfunction "2_2") (pintype "input"))
    )
    (net (code "51") (name "OSC_IN") (class "Default")
      (node (ref "U1") (pin "12") (pinfunction "OSC_IN_12") (pintype "unspecified"))
      (node (ref "U9") (pin "12") (pinfunction "OSC_IN_12") (pintype "unspecified"))
      (node (ref "X1") (pin "2") (pinfunction "OSC2_2") (pintype "input"))
    )
    (net (code "52") (name "OSC_OUT") (class "Default")
      (node (ref "U1") (pin "13") (pinfunction "OSC_OUT_13") (pintype "unspecified"))
      (node (ref "U9") (pin "13") (pinfunction "OSC_OUT_13") (pintype "unspecified"))
      (node (ref "X1") (pin "1") (pinfunction "OSC1_1") (pintype "input"))
    )
    (net (code "53") (name "POWER_LED") (class "Default")
      (node (ref "R3") (pin "1") (pinfunction "1_1") (pintype "input"))
      (node (ref "U1") (pin "95") (pinfunction "PB8_95") (pintype "unspecified"))
      (node (ref "U9") (pin "95") (pinfunction "PB8_95") (pintype "unspecified"))
    )
    (net (code "54") (name "SENSE_V5") (class "Default")
      (node (ref "R14") (pin "1") (pinfunction "1_1") (pintype "input"))
      (node (ref "R15") (pin "2") (pinfunction "2_2") (pintype "input"))
      (node (ref "U1") (pin "35") (pinfunction "PB0_35") (pintype "unspecified"))
      (node (ref "U9") (pin "35") (pinfunction "PB0_35") (pintype "unspecified"))
    )
    (net (code "55") (name "SOCKET_A0") (class "Default")
      (node (ref "H1L") (pin "9") (pinfunction "9_9") (pintype "unspecified"))
      (node (ref "H4R") (pin "20") (pinfunction "20_20") (pintype "unspecified"))
      (node (ref "H5R") (pin "20") (pinfunction "20_20") (pintype "unspecified"))
      (node (ref "U1") (pin "15") (pinfunction "PC0_15") (pintype "unspecified"))
      (node (ref "U2") (pin "25") (pinfunction "A0_25") (pintype "unspecified"))
      (node (ref "U3") (pin "25") (pinfunction "A0_25") (pintype "unspecified"))
      (node (ref "U9") (pin "15") (pinfunction "PC0_15") (pintype "unspecified"))
    )
    (net (code "56") (name "SOCKET_A1") (class "Default")
      (node (ref "H1L") (pin "8") (pinfunction "8_8") (pintype "unspecified"))
      (node (ref "H4R") (pin "19") (pinfunction "19_19") (pintype "unspecified"))
      (node (ref "H5R") (pin "19") (pinfunction "19_19") (pintype "unspecified"))
      (node (ref "U1") (pin "16") (pinfunction "PC1_16") (pintype "unspecified"))
      (node (ref "U2") (pin "24") (pinfunction "A1_24") (pintype "unspecified"))
      (node (ref "U3") (pin "24") (pinfunction "A1_24") (pintype "unspecified"))
      (node (ref "U9") (pin "16") (pinfunction "PC1_16") (pintype "unspecified"))
    )
    (net (code "57") (name "SOCKET_A2") (class "Default")
      (node (ref "H1L") (pin "7") (pinfunction "7_7") (pintype "unspecified"))
      (node (ref "H4R") (pin "18") (pinfunction "18_18") (pintype "unspecified"))
      (node (ref "H5R") (pin "18") (pinfunction "18_18") (pintype "unspecified"))
      (node (ref "U1") (pin "17") (pinfunction "PC2_17") (pintype "unspecified"))
      (node (ref "U2") (pin "23") (pinfunction "A2_23") (pintype "unspecified"))
      (node (ref "U3") (pin "23") (pinfunction "A2_23") (pintype "unspecified"))
      (node (ref "U9") (pin "17") (pinfunction "PC2_17") (pintype "unspecified"))
    )
    (net (code "58") (name "SOCKET_A3") (class "Default")
      (node (ref "H1L") (pin "6") (pinfunction "6_6") (pintype "unspecified"))
      (node (ref "H4R") (pin "17") (pinfunction "17_17") (pintype "unspecified"))
      (node (ref "H5R") (pin "17") (pinfunction "17_17") (pintype "unspecified"))
      (node (ref "U1") (pin "18") (pinfunction "PC3_18") (pintype "unspecified"))
      (node (ref "U2") (pin "22") (pinfunction "A3_22") (pintype "unspecified"))
      (node (ref "U3") (pin "22") (pinfunction "A3_22") (pintype "unspecified"))
      (node (ref "U9") (pin "18") (pinfunction "PC3_18") (pintype "unspecified"))
    )
    (net (code "59") (name "SOCKET_A4") (class "Default")
      (node (ref "H1L") (pin "5") (pinfunction "5_5") (pintype "unspecified"))
      (node (ref "H4R") (pin "16") (pinfunction "16_16") (pintype "unspecified"))
      (node (ref "H5R") (pin "16") (pinfunction "16_16") (pintype "unspecified"))
      (node (ref "U1") (pin "33") (pinfunction "PC4_33") (pintype "unspecified"))
      (node (ref "U2") (pin "21") (pinfunction "A4_21") (pintype "unspecified"))
      (node (ref "U3") (pin "21") (pinfunction "A4_21") (pintype "unspecified"))
      (node (ref "U9") (pin "33") (pinfunction "PC4_33") (pintype "unspecified"))
    )
    (net (code "60") (name "SOCKET_A5") (class "Default")
      (node (ref "H1L") (pin "4") (pinfunction "4_4") (pintype "unspecified"))
      (node (ref "H4R") (pin "15") (pinfunction "15_15") (pintype "unspecified"))
      (node (ref "H5R") (pin "15") (pinfunction "15_15") (pintype "unspecified"))
      (node (ref "U1") (pin "34") (pinfunction "PC5_34") (pintype "unspecified"))
      (node (ref "U2") (pin "20") (pinfunction "A5_20") (pintype "unspecified"))
      (node (ref "U3") (pin "20") (pinfunction "A5_20") (pintype "unspecified"))
      (node (ref "U9") (pin "34") (pinfunction "PC5_34") (pintype "unspecified"))
    )
    (net (code "61") (name "SOCKET_A6") (class "Default")
      (node (ref "H1L") (pin "3") (pinfunction "3_3") (pintype "unspecified"))
      (node (ref "H4R") (pin "14") (pinfunction "14_14") (pintype "unspecified"))
      (node (ref "H5R") (pin "14") (pinfunction "14_14") (pintype "unspecified"))
      (node (ref "U1") (pin "63") (pinfunction "PC6_63") (pintype "unspecified"))
      (node (ref "U2") (pin "19") (pinfunction "A6_19") (pintype "unspecified"))
      (node (ref "U3") (pin "19") (pinfunction "A6_19") (pintype "unspecified"))
      (node (ref "U9") (pin "63") (pinfunction "PC6_63") (pintype "unspecified"))
    )
    (net (code "62") (name "SOCKET_A7") (class "Default")
      (node (ref "H1L") (pin "2") (pinfunction "2_2") (pintype "unspecified"))
      (node (ref "H4R") (pin "13") (pinfunction "13_13") (pintype "unspecified"))
      (node (ref "H5R") (pin "13") (pinfunction "13_13") (pintype "unspecified"))
      (node (ref "U1") (pin "64") (pinfunction "PC7_64") (pintype "unspecified"))
      (node (ref "U2") (pin "18") (pinfunction "A7_18") (pintype "unspecified"))
      (node (ref "U3") (pin "18") (pinfunction "A7_18") (pintype "unspecified"))
      (node (ref "U9") (pin "64") (pinfunction "PC7_64") (pintype "unspecified"))
    )
    (net (code "63") (name "SOCKET_A8") (class "Default")
      (node (ref "H1R") (pin "1") (pinfunction "1_1") (pintype "unspecified"))
      (node (ref "H4R") (pin "12") (pinfunction "12_12") (pintype "unspecified"))
      (node (ref "H5R") (pin "12") (pinfunction "12_12") (pintype "unspecified"))
      (node (ref "U1") (pin "65") (pinfunction "PC8_65") (pintype "unspecified"))
      (node (ref "U2") (pin "8") (pinfunction "A8_8") (pintype "unspecified"))
      (node (ref "U3") (pin "8") (pinfunction "A8_8") (pintype "unspecified"))
      (node (ref "U9") (pin "65") (pinfunction "PC8_65") (pintype "unspecified"))
    )
    (net (code "64") (name "SOCKET_A9") (class "Default")
      (node (ref "H1R") (pin "2") (pinfunction "2_2") (pintype "unspecified"))
      (node (ref "H4R") (pin "10") (pinfunction "10_10") (pintype "unspecified"))
      (node (ref "H5R") (pin "10") (pinfunction "10_10") (pintype "unspecified"))
      (node (ref "U1") (pin "66") (pinfunction "PC9_66") (pintype "unspecified"))
      (node (ref "U2") (pin "7") (pinfunction "A9_7") (pintype "unspecified"))
      (node (ref "U3") (pin "7") (pinfunction "A9_7") (pintype "unspecified"))
      (node (ref "U9") (pin "66") (pinfunction "PC9_66") (pintype "unspecified"))
    )
    (net (code "65") (name "SOCKET_A10") (class "Default")
      (node (ref "H1R") (pin "3") (pinfunction "3_3") (pintype "unspecified"))
      (node (ref "H4R") (pin "9") (pinfunction "9_9") (pintype "unspecified"))
      (node (ref "H5R") (pin "9") (pinfunction "9_9") (pintype "unspecified"))
      (node (ref "U1") (pin "78") (pinfunction "PC10_78") (pintype "unspecified"))
      (node (ref "U2") (pin "6") (pinfunction "A10_6") (pintype "unspecified"))
      (node (ref "U3") (pin "6") (pinfunction "A10_6") (pintype "unspecified"))
      (node (ref "U9") (pin "78") (pinfunction "PC10_78") (pintype "unspecified"))
    )
    (net (code "66") (name "SOCKET_A11") (class "Default")
      (node (ref "H1R") (pin "4") (pinfunction "4_4") (pintype "unspecified"))
      (node (ref "H4R") (pin "8") (pinfunction "8_8") (pintype "unspecified"))
      (node (ref "H5R") (pin "8") (pinfunction "8_8") (pintype "unspecified"))
      (node (ref "U1") (pin "79") (pinfunction "PC11_79") (pintype "unspecified"))
      (node (ref "U2") (pin "5") (pinfunction "A11_5") (pintype "unspecified"))
      (node (ref "U3") (pin "5") (pinfunction "A11_5") (pintype "unspecified"))
      (node (ref "U9") (pin "79") (pinfunction "PC11_79") (pintype "unspecified"))
    )
    (net (code "67") (name "SOCKET_A12") (class "Default")
      (node (ref "H1R") (pin "5") (pinfunction "5_5") (pintype "unspecified"))
      (node (ref "H4R") (pin "7") (pinfunction "7_7") (pintype "unspecified"))
      (node (ref "H5R") (pin "7") (pinfunction "7_7") (pintype "unspecified"))
      (node (ref "U1") (pin "80") (pinfunction "PC12_80") (pintype "unspecified"))
      (node (ref "U2") (pin "4") (pinfunction "A12_4") (pintype "unspecified"))
      (node (ref "U3") (pin "4") (pinfunction "A12_4") (pintype "unspecified"))
      (node (ref "U9") (pin "80") (pinfunction "PC12_80") (pintype "unspecified"))
    )
    (net (code "68") (name "SOCKET_A13") (class "Default")
      (node (ref "H1R") (pin "6") (pinfunction "6_6") (pintype "unspecified"))
      (node (ref "H4R") (pin "6") (pinfunction "6_6") (pintype "unspecified"))
      (node (ref "H5R") (pin "6") (pinfunction "6_6") (pintype "unspecified"))
      (node (ref "U1") (pin "24") (pinfunction "PA1_24") (pintype "unspecified"))
      (node (ref "U1") (pin "7") (pinfunction "PC13-TAMPER-RTC_7") (pintype "unspecified"))
      (node (ref "U2") (pin "3") (pinfunction "A13_3") (pintype "unspecified"))
      (node (ref "U3") (pin "3") (pinfunction "A13_3") (pintype "unspecified"))
      (node (ref "U9") (pin "24") (pinfunction "PA1_24") (pintype "unspecified"))
      (node (ref "U9") (pin "7") (pinfunction "PC13_TAMPER_RTC_7") (pintype "unspecified"))
    )
    (net (code "69") (name "SOCKET_A14") (class "Default")
      (node (ref "H1R") (pin "7") (pinfunction "7_7") (pintype "unspecified"))
      (node (ref "H4R") (pin "5") (pinfunction "5_5") (pintype "unspecified"))
      (node (ref "H5R") (pin "5") (pinfunction "5_5") (pintype "unspecified"))
      (node (ref "U1") (pin "25") (pinfunction "PA2_25") (pintype "unspecified"))
      (node (ref "U1") (pin "8") (pinfunction "PC14-OSC32_IN_8") (pintype "unspecified"))
      (node (ref "U2") (pin "2") (pinfunction "A14_2") (pintype "unspecified"))
      (node (ref "U3") (pin "2") (pinfunction "A14_2") (pintype "unspecified"))
      (node (ref "U9") (pin "25") (pinfunction "PA2_25") (pintype "unspecified"))
      (node (ref "U9") (pin "8") (pinfunction "PC14_OSC32_IN_8") (pintype "unspecified"))
    )
    (net (code "70") (name "SOCKET_A15") (class "Default")
      (node (ref "H1R") (pin "8") (pinfunction "8_8") (pintype "unspecified"))
      (node (ref "H4R") (pin "4") (pinfunction "4_4") (pintype "unspecified"))
      (node (ref "H5R") (pin "4") (pinfunction "4_4") (pintype "unspecified"))
      (node (ref "U1") (pin "26") (pinfunction "PA3_26") (pintype "unspecified"))
      (node (ref "U1") (pin "9") (pinfunction "PC15-OSC32_OUT_9") (pintype "unspecified"))
      (node (ref "U2") (pin "1") (pinfunction "A15_1") (pintype "unspecified"))
      (node (ref "U3") (pin "1") (pinfunction "A15_1") (pintype "unspecified"))
      (node (ref "U9") (pin "26") (pinfunction "PA3_26") (pintype "unspecified"))
      (node (ref "U9") (pin "9") (pinfunction "PC15_OSC32_OUT_9") (pintype "unspecified"))
    )
    (net (code "71") (name "SOCKET_A16") (class "Default")
      (node (ref "H1R") (pin "9") (pinfunction "9_9") (pintype "unspecified"))
      (node (ref "H4R") (pin "3") (pinfunction "3_3") (pintype "unspecified"))
      (node (ref "H5R") (pin "3") (pinfunction "3_3") (pintype "unspecified"))
      (node (ref "U1") (pin "29") (pinfunction "PA4_29") (pintype "unspecified"))
      (node (ref "U2") (pin "48") (pinfunction "A16_48") (pintype "unspecified"))
      (node (ref "U3") (pin "48") (pinfunction "A16_48") (pintype "unspecified"))
      (node (ref "U9") (pin "29") (pinfunction "PA4_29") (pintype "unspecified"))
    )
    (net (code "72") (name "SOCKET_A17") (class "Default")
      (node (ref "H1L") (pin "1") (pinfunction "1_1") (pintype "unspecified"))
      (node (ref "H4R") (pin "2") (pinfunction "2_2") (pintype "unspecified"))
      (node (ref "H9") (pin "1") (pinfunction "1_1") (pintype "input"))
      (node (ref "R16") (pin "2") (pinfunction "2_2") (pintype "input"))
    )
    (net (code "73") (name "SOCKET_A18") (class "Default")
      (node (ref "H7") (pin "1") (pinfunction "1_1") (pintype "unspecified"))
      (node (ref "R9") (pin "2") (pinfunction "2_2") (pintype "input"))
    )
    (net (code "74") (name "SOCKET_A19") (class "Default")
      (node (ref "H8") (pin "1") (pinfunction "1_1") (pintype "unspecified"))
      (node (ref "R8") (pin "2") (pinfunction "2_2") (pintype "input"))
    )
    (net (code "75") (name "SOCKET_CE") (class "Default")
      (node (ref "H1L") (pin "10") (pinfunction "10_10") (pintype "unspecified"))
      (node (ref "U11") (pin "3") (pinfunction "B_3") (pintype "unspecified"))
    )
    (net (code "76") (name "SOCKET_D0") (class "Default")
      (node (ref "H1L") (pin "13") (pinfunction "13_13") (pintype "unspecified"))
      (node (ref "H3L") (pin "19") (pinfunction "19_19") (pintype "unspecified"))
      (node (ref "H7L") (pin "19") (pinfunction "19_19") (pintype "unspecified"))
      (node (ref "U5") (pin "23") (pinfunction "4Y4_23") (pintype "unspecified"))
    )
    (net (code "77") (name "SOCKET_D1") (class "Default")
      (node (ref "H1L") (pin "15") (pinfunction "15_15") (pintype "unspecified"))
      (node (ref "H3L") (pin "18") (pinfunction "18_18") (pintype "unspecified"))
      (node (ref "H7L") (pin "18") (pinfunction "18_18") (pintype "unspecified"))
      (node (ref "U5") (pin "22") (pinfunction "4Y3_22") (pintype "unspecified"))
    )
    (net (code "78") (name "SOCKET_D2") (class "Default")
      (node (ref "H1L") (pin "17") (pinfunction "17_17") (pintype "unspecified"))
      (node (ref "H3L") (pin "17") (pinfunction "17_17") (pintype "unspecified"))
      (node (ref "H7L") (pin "17") (pinfunction "17_17") (pintype "unspecified"))
      (node (ref "U5") (pin "20") (pinfunction "4Y2_20") (pintype "unspecified"))
    )
    (net (code "79") (name "SOCKET_D3") (class "Default")
      (node (ref "H1L") (pin "19") (pinfunction "19_19") (pintype "unspecified"))
      (node (ref "H3L") (pin "16") (pinfunction "16_16") (pintype "unspecified"))
      (node (ref "H7L") (pin "16") (pinfunction "16_16") (pintype "unspecified"))
      (node (ref "U5") (pin "19") (pinfunction "4Y1_19") (pintype "unspecified"))
    )
    (net (code "80") (name "SOCKET_D4") (class "Default")
      (node (ref "H1R") (pin "19") (pinfunction "19_19") (pintype "unspecified"))
      (node (ref "H3L") (pin "15") (pinfunction "15_15") (pintype "unspecified"))
      (node (ref "H7L") (pin "15") (pinfunction "15_15") (pintype "unspecified"))
      (node (ref "U5") (pin "17") (pinfunction "3Y4_17") (pintype "unspecified"))
    )
    (net (code "81") (name "SOCKET_D5") (class "Default")
      (node (ref "H1R") (pin "17") (pinfunction "17_17") (pintype "unspecified"))
      (node (ref "H3L") (pin "14") (pinfunction "14_14") (pintype "unspecified"))
      (node (ref "H7L") (pin "14") (pinfunction "14_14") (pintype "unspecified"))
      (node (ref "U5") (pin "16") (pinfunction "3Y3_16") (pintype "unspecified"))
    )
    (net (code "82") (name "SOCKET_D6") (class "Default")
      (node (ref "H1R") (pin "15") (pinfunction "15_15") (pintype "unspecified"))
      (node (ref "H3L") (pin "13") (pinfunction "13_13") (pintype "unspecified"))
      (node (ref "H7L") (pin "13") (pinfunction "13_13") (pintype "unspecified"))
      (node (ref "U5") (pin "14") (pinfunction "3Y2_14") (pintype "unspecified"))
    )
    (net (code "83") (name "SOCKET_D7") (class "Default")
      (node (ref "H1R") (pin "13") (pinfunction "13_13") (pintype "unspecified"))
      (node (ref "H3L") (pin "12") (pinfunction "12_12") (pintype "unspecified"))
      (node (ref "H7L") (pin "12") (pinfunction "12_12") (pintype "unspecified"))
      (node (ref "U5") (pin "13") (pinfunction "3Y1_13") (pintype "unspecified"))
    )
    (net (code "84") (name "SOCKET_D8") (class "Default")
      (node (ref "H1L") (pin "14") (pinfunction "14_14") (pintype "unspecified"))
      (node (ref "H3L") (pin "10") (pinfunction "10_10") (pintype "unspecified"))
      (node (ref "H7L") (pin "10") (pinfunction "10_10") (pintype "unspecified"))
      (node (ref "U5") (pin "12") (pinfunction "2Y4_12") (pintype "unspecified"))
    )
    (net (code "85") (name "SOCKET_D9") (class "Default")
      (node (ref "H1L") (pin "16") (pinfunction "16_16") (pintype "unspecified"))
      (node (ref "H3L") (pin "9") (pinfunction "9_9") (pintype "unspecified"))
      (node (ref "H7L") (pin "9") (pinfunction "9_9") (pintype "unspecified"))
      (node (ref "U5") (pin "11") (pinfunction "2Y3_11") (pintype "unspecified"))
    )
    (net (code "86") (name "SOCKET_D10") (class "Default")
      (node (ref "H1L") (pin "18") (pinfunction "18_18") (pintype "unspecified"))
      (node (ref "H3L") (pin "8") (pinfunction "8_8") (pintype "unspecified"))
      (node (ref "H7L") (pin "8") (pinfunction "8_8") (pintype "unspecified"))
      (node (ref "U5") (pin "9") (pinfunction "2Y2_9") (pintype "unspecified"))
    )
    (net (code "87") (name "SOCKET_D11") (class "Default")
      (node (ref "H1L") (pin "20") (pinfunction "20_20") (pintype "unspecified"))
      (node (ref "H3L") (pin "7") (pinfunction "7_7") (pintype "unspecified"))
      (node (ref "H7L") (pin "7") (pinfunction "7_7") (pintype "unspecified"))
      (node (ref "U5") (pin "8") (pinfunction "2Y1_8") (pintype "unspecified"))
    )
    (net (code "88") (name "SOCKET_D12") (class "Default")
      (node (ref "H1R") (pin "18") (pinfunction "18_18") (pintype "unspecified"))
      (node (ref "H3L") (pin "6") (pinfunction "6_6") (pintype "unspecified"))
      (node (ref "H7L") (pin "6") (pinfunction "6_6") (pintype "unspecified"))
      (node (ref "U5") (pin "6") (pinfunction "1Y4_6") (pintype "unspecified"))
    )
    (net (code "89") (name "SOCKET_D13") (class "Default")
      (node (ref "H1R") (pin "16") (pinfunction "16_16") (pintype "unspecified"))
      (node (ref "H3L") (pin "5") (pinfunction "5_5") (pintype "unspecified"))
      (node (ref "H7L") (pin "5") (pinfunction "5_5") (pintype "unspecified"))
      (node (ref "U5") (pin "5") (pinfunction "1Y3_5") (pintype "unspecified"))
    )
    (net (code "90") (name "SOCKET_D14") (class "Default")
      (node (ref "H1R") (pin "14") (pinfunction "14_14") (pintype "unspecified"))
      (node (ref "H3L") (pin "4") (pinfunction "4_4") (pintype "unspecified"))
      (node (ref "H7L") (pin "4") (pinfunction "4_4") (pintype "unspecified"))
      (node (ref "U5") (pin "3") (pinfunction "1Y2_3") (pintype "unspecified"))
    )
    (net (code "91") (name "SOCKET_D15") (class "Default")
      (node (ref "H1R") (pin "12") (pinfunction "12_12") (pintype "unspecified"))
      (node (ref "H3L") (pin "3") (pinfunction "3_3") (pintype "unspecified"))
      (node (ref "H7L") (pin "3") (pinfunction "3_3") (pintype "unspecified"))
      (node (ref "U5") (pin "2") (pinfunction "1Y1_2") (pintype "unspecified"))
    )
    (net (code "92") (name "SOCKET_D16") (class "Default")
      (node (ref "H2L") (pin "2") (pinfunction "2_2") (pintype "unspecified"))
      (node (ref "H4L") (pin "19") (pinfunction "19_19") (pintype "unspecified"))
      (node (ref "H5L") (pin "19") (pinfunction "19_19") (pintype "unspecified"))
      (node (ref "U6") (pin "23") (pinfunction "4Y4_23") (pintype "unspecified"))
    )
    (net (code "93") (name "SOCKET_D17") (class "Default")
      (node (ref "H2L") (pin "4") (pinfunction "4_4") (pintype "unspecified"))
      (node (ref "H4L") (pin "18") (pinfunction "18_18") (pintype "unspecified"))
      (node (ref "H5L") (pin "18") (pinfunction "18_18") (pintype "unspecified"))
      (node (ref "U6") (pin "22") (pinfunction "4Y3_22") (pintype "unspecified"))
    )
    (net (code "94") (name "SOCKET_D18") (class "Default")
      (node (ref "H2L") (pin "6") (pinfunction "6_6") (pintype "unspecified"))
      (node (ref "H4L") (pin "17") (pinfunction "17_17") (pintype "unspecified"))
      (node (ref "H5L") (pin "17") (pinfunction "17_17") (pintype "unspecified"))
      (node (ref "U6") (pin "20") (pinfunction "4Y2_20") (pintype "unspecified"))
    )
    (net (code "95") (name "SOCKET_D19") (class "Default")
      (node (ref "H2L") (pin "8") (pinfunction "8_8") (pintype "unspecified"))
      (node (ref "H4L") (pin "16") (pinfunction "16_16") (pintype "unspecified"))
      (node (ref "H5L") (pin "16") (pinfunction "16_16") (pintype "unspecified"))
      (node (ref "U6") (pin "19") (pinfunction "4Y1_19") (pintype "unspecified"))
    )
    (net (code "96") (name "SOCKET_D20") (class "Default")
      (node (ref "H2R") (pin "8") (pinfunction "8_8") (pintype "unspecified"))
      (node (ref "H4L") (pin "15") (pinfunction "15_15") (pintype "unspecified"))
      (node (ref "H5L") (pin "15") (pinfunction "15_15") (pintype "unspecified"))
      (node (ref "U6") (pin "17") (pinfunction "3Y4_17") (pintype "unspecified"))
    )
    (net (code "97") (name "SOCKET_D21") (class "Default")
      (node (ref "H2R") (pin "6") (pinfunction "6_6") (pintype "unspecified"))
      (node (ref "H4L") (pin "14") (pinfunction "14_14") (pintype "unspecified"))
      (node (ref "H5L") (pin "14") (pinfunction "14_14") (pintype "unspecified"))
      (node (ref "U6") (pin "16") (pinfunction "3Y3_16") (pintype "unspecified"))
    )
    (net (code "98") (name "SOCKET_D22") (class "Default")
      (node (ref "H2R") (pin "4") (pinfunction "4_4") (pintype "unspecified"))
      (node (ref "H4L") (pin "13") (pinfunction "13_13") (pintype "unspecified"))
      (node (ref "H5L") (pin "13") (pinfunction "13_13") (pintype "unspecified"))
      (node (ref "U6") (pin "14") (pinfunction "3Y2_14") (pintype "unspecified"))
    )
    (net (code "99") (name "SOCKET_D23") (class "Default")
      (node (ref "H2R") (pin "2") (pinfunction "2_2") (pintype "unspecified"))
      (node (ref "H4L") (pin "12") (pinfunction "12_12") (pintype "unspecified"))
      (node (ref "H5L") (pin "12") (pinfunction "12_12") (pintype "unspecified"))
      (node (ref "U6") (pin "13") (pinfunction "3Y1_13") (pintype "unspecified"))
    )
    (net (code "100") (name "SOCKET_D24") (class "Default")
      (node (ref "H2L") (pin "3") (pinfunction "3_3") (pintype "unspecified"))
      (node (ref "H4L") (pin "10") (pinfunction "10_10") (pintype "unspecified"))
      (node (ref "H5L") (pin "10") (pinfunction "10_10") (pintype "unspecified"))
      (node (ref "U6") (pin "12") (pinfunction "2Y4_12") (pintype "unspecified"))
    )
    (net (code "101") (name "SOCKET_D25") (class "Default")
      (node (ref "H2L") (pin "5") (pinfunction "5_5") (pintype "unspecified"))
      (node (ref "H4L") (pin "9") (pinfunction "9_9") (pintype "unspecified"))
      (node (ref "H5L") (pin "9") (pinfunction "9_9") (pintype "unspecified"))
      (node (ref "U6") (pin "11") (pinfunction "2Y3_11") (pintype "unspecified"))
    )
    (net (code "102") (name "SOCKET_D26") (class "Default")
      (node (ref "H2L") (pin "7") (pinfunction "7_7") (pintype "unspecified"))
      (node (ref "H4L") (pin "8") (pinfunction "8_8") (pintype "unspecified"))
      (node (ref "H5L") (pin "8") (pinfunction "8_8") (pintype "unspecified"))
      (node (ref "U6") (pin "9") (pinfunction "2Y2_9") (pintype "unspecified"))
    )
    (net (code "103") (name "SOCKET_D27") (class "Default")
      (node (ref "H2L") (pin "9") (pinfunction "9_9") (pintype "unspecified"))
      (node (ref "H4L") (pin "7") (pinfunction "7_7") (pintype "unspecified"))
      (node (ref "H5L") (pin "7") (pinfunction "7_7") (pintype "unspecified"))
      (node (ref "U6") (pin "8") (pinfunction "2Y1_8") (pintype "unspecified"))
    )
    (net (code "104") (name "SOCKET_D28") (class "Default")
      (node (ref "H2R") (pin "7") (pinfunction "7_7") (pintype "unspecified"))
      (node (ref "H4L") (pin "6") (pinfunction "6_6") (pintype "unspecified"))
      (node (ref "H5L") (pin "6") (pinfunction "6_6") (pintype "unspecified"))
      (node (ref "U6") (pin "6") (pinfunction "1Y4_6") (pintype "unspecified"))
    )
    (net (code "105") (name "SOCKET_D29") (class "Default")
      (node (ref "H2R") (pin "5") (pinfunction "5_5") (pintype "unspecified"))
      (node (ref "H4L") (pin "5") (pinfunction "5_5") (pintype "unspecified"))
      (node (ref "H5L") (pin "5") (pinfunction "5_5") (pintype "unspecified"))
      (node (ref "U6") (pin "5") (pinfunction "1Y3_5") (pintype "unspecified"))
    )
    (net (code "106") (name "SOCKET_D30") (class "Default")
      (node (ref "H2R") (pin "3") (pinfunction "3_3") (pintype "unspecified"))
      (node (ref "H4L") (pin "4") (pinfunction "4_4") (pintype "unspecified"))
      (node (ref "H5L") (pin "4") (pinfunction "4_4") (pintype "unspecified"))
      (node (ref "U6") (pin "3") (pinfunction "1Y2_3") (pintype "unspecified"))
    )
    (net (code "107") (name "SOCKET_D31") (class "Default")
      (node (ref "H2R") (pin "1") (pinfunction "1_1") (pintype "unspecified"))
      (node (ref "H4L") (pin "3") (pinfunction "3_3") (pintype "unspecified"))
      (node (ref "H5L") (pin "3") (pinfunction "3_3") (pintype "unspecified"))
      (node (ref "U1") (pin "51") (pinfunction "PB12_51") (pintype "unspecified"))
      (node (ref "U6") (pin "2") (pinfunction "1Y1_2") (pintype "unspecified"))
      (node (ref "U9") (pin "51") (pinfunction "PB12_51") (pintype "unspecified"))
    )
    (net (code "108") (name "SOCKET_OE") (class "Default")
      (node (ref "H1L") (pin "12") (pinfunction "12_12") (pintype "unspecified"))
      (node (ref "H3L") (pin "20") (pinfunction "20_20") (pintype "unspecified"))
      (node (ref "H5L") (pin "20") (pinfunction "20_20") (pintype "unspecified"))
      (node (ref "H7L") (pin "20") (pinfunction "20_20") (pintype "unspecified"))
      (node (ref "J1") (pin "1") (pinfunction "1_1") (pintype "unspecified"))
      (node (ref "U1") (pin "54") (pinfunction "PB15_54") (pintype "unspecified"))
      (node (ref "U11") (pin "1") (pinfunction "A_1") (pintype "unspecified"))
      (node (ref "U9") (pin "54") (pinfunction "PB15_54") (pintype "unspecified"))
    )
    (net (code "109") (name "SOCKET_V5") (class "Default")
      (node (ref "D2") (pin "2") (pinfunction "+_2") (pintype "unspecified"))
      (node (ref "H1R") (pin "20") (pinfunction "20_20") (pintype "unspecified"))
      (node (ref "H2R") (pin "9") (pinfunction "9_9") (pintype "unspecified"))
      (node (ref "H4R") (pin "1") (pinfunction "1_1") (pintype "unspecified"))
      (node (ref "H5R") (pin "1") (pinfunction "1_1") (pintype "unspecified"))
      (node (ref "R14") (pin "2") (pinfunction "2_2") (pintype "input"))
    )
    (net (code "110") (name "STM_BOOT0") (class "Default")
      (node (ref "H5") (pin "1") (pinfunction "1_1") (pintype "unspecified"))
      (node (ref "R6") (pin "1") (pinfunction "1_1") (pintype "input"))
      (node (ref "SW1") (pin "2") (pinfunction "2_2") (pintype "unspecified"))
      (node (ref "U1") (pin "91") (pinfunction "PB5_91") (pintype "unspecified"))
      (node (ref "U1") (pin "94") (pinfunction "BOOT0_94") (pintype "unspecified"))
      (node (ref "U9") (pin "91") (pinfunction "PB5_91") (pintype "unspecified"))
      (node (ref "U9") (pin "94") (pinfunction "BOOT0_94") (pintype "unspecified"))
    )
    (net (code "111") (name "STM_NRST") (class "Default")
      (node (ref "H6") (pin "5") (pinfunction "5_5") (pintype "input"))
      (node (ref "U1") (pin "14") (pinfunction "NRST_14") (pintype "unspecified"))
      (node (ref "U9") (pin "14") (pinfunction "NRST_14") (pintype "unspecified"))
    )
    (net (code "112") (name "STM_SWCLK_TCK") (class "Default")
      (node (ref "H6") (pin "2") (pinfunction "2_2") (pintype "input"))
      (node (ref "U1") (pin "76") (pinfunction "PA14_76") (pintype "unspecified"))
      (node (ref "U9") (pin "76") (pinfunction "PA14_76") (pintype "unspecified"))
    )
    (net (code "113") (name "STM_SWDIO_TMS") (class "Default")
      (node (ref "H6") (pin "4") (pinfunction "4_4") (pintype "input"))
      (node (ref "U1") (pin "72") (pinfunction "PA13_72") (pintype "unspecified"))
      (node (ref "U9") (pin "72") (pinfunction "PA13_72") (pintype "unspecified"))
    )
    (net (code "114") (name "STM_SWO_TDO") (class "Default")
      (node (ref "H6") (pin "6") (pinfunction "6_6") (pintype "input"))
      (node (ref "U1") (pin "89") (pinfunction "PB3_89") (pintype "unspecified"))
      (node (ref "U9") (pin "89") (pinfunction "PB3_89") (pintype "unspecified"))
    )
    (net (code "115") (name "USB_CC1") (class "Default")
      (node (ref "R5") (pin "1") (pinfunction "1_1") (pintype "input"))
      (node (ref "U1") (pin "67") (pinfunction "PA8_67") (pintype "unspecified"))
      (node (ref "U9") (pin "67") (pinfunction "PA8_67") (pintype "unspecified"))
      (node (ref "USBC1") (pin "A5") (pinfunction "CC1_A5") (pintype "unspecified"))
      (node (ref "USBC2") (pin "A5") (pinfunction "CC1_A5") (pintype "unspecified"))
    )
    (net (code "116") (name "USB_CC2") (class "Default")
      (node (ref "R4") (pin "1") (pinfunction "1_1") (pintype "input"))
      (node (ref "U1") (pin "69") (pinfunction "PA10_69") (pintype "unspecified"))
      (node (ref "U9") (pin "69") (pinfunction "PA10_69") (pintype "unspecified"))
      (node (ref "USBC1") (pin "B5") (pinfunction "CC2_B5") (pintype "unspecified"))
      (node (ref "USBC2") (pin "B5") (pinfunction "CC2_B5") (pintype "unspecified"))
    )
    (net (code "117") (name "USB_DM") (class "Default")
      (node (ref "U1") (pin "70") (pinfunction "PA11_70") (pintype "unspecified"))
      (node (ref "U9") (pin "70") (pinfunction "PA11_70") (pintype "unspecified"))
      (node (ref "USBC1") (pin "A7") (pinfunction "DN1_A7") (pintype "unspecified"))
      (node (ref "USBC1") (pin "B7") (pinfunction "DN2_B7") (pintype "unspecified"))
      (node (ref "USBC2") (pin "A7") (pinfunction "D-_A7") (pintype "unspecified"))
      (node (ref "USBC2") (pin "B7") (pinfunction "D-_B7") (pintype "unspecified"))
    )
    (net (code "118") (name "USB_DP") (class "Default")
      (node (ref "U1") (pin "71") (pinfunction "PA12_71") (pintype "unspecified"))
      (node (ref "U9") (pin "71") (pinfunction "PA12_71") (pintype "unspecified"))
      (node (ref "USBC1") (pin "A6") (pinfunction "DP1_A6") (pintype "unspecified"))
      (node (ref "USBC1") (pin "B6") (pinfunction "DP2_B6") (pintype "unspecified"))
      (node (ref "USBC2") (pin "A6") (pinfunction "D+_A6") (pintype "unspecified"))
      (node (ref "USBC2") (pin "B6") (pinfunction "D+_B6") (pintype "unspecified"))
    )
    (net (code "119") (name "USB_V5") (class "Default")
      (node (ref "D1") (pin "2") (pinfunction "+_2") (pintype "unspecified"))
      (node (ref "U1") (pin "68") (pinfunction "PA9_68") (pintype "unspecified"))
      (node (ref "U9") (pin "68") (pinfunction "PA9_68") (pintype "unspecified"))
      (node (ref "USBC1") (pin "A4B9") (pinfunction "VBUS_A4B9") (pintype "unspecified"))
      (node (ref "USBC1") (pin "B4A9") (pinfunction "VBUS_B4A9") (pintype "unspecified"))
      (node (ref "USBC2") (pin "A4") (pinfunction "VBUS_A4") (pintype "unspecified"))
      (node (ref "USBC2") (pin "A9") (pinfunction "VBUS_A9") (pintype "unspecified"))
      (node (ref "USBC2") (pin "B4") (pinfunction "VBUS_B4") (pintype "unspecified"))
      (node (ref "USBC2") (pin "B9") (pinfunction "VBUS_B9") (pintype "unspecified"))
    )
    (net (code "120") (name "V3P3") (class "Default")
      (node (ref "C4") (pin "1") (pinfunction "1_1") (pintype "input"))
      (node (ref "C5") (pin "2") (pinfunction "2_2") (pintype "unspecified"))
      (node (ref "C6") (pin "1") (pinfunction "1_1") (pintype "input"))
      (node (ref "C7") (pin "1") (pinfunction "1_1") (pintype "input"))
      (node (ref "C8") (pin "1") (pinfunction "1_1") (pintype "input"))
      (node (ref "H6") (pin "1") (pinfunction "1_1") (pintype "input"))
      (node (ref "SW1") (pin "1") (pinfunction "1_1") (pintype "unspecified"))
      (node (ref "U1") (pin "100") (pinfunction "VDD_3_100") (pintype "unspecified"))
      (node (ref "U1") (pin "11") (pinfunction "VDD_5_11") (pintype "unspecified"))
      (node (ref "U1") (pin "21") (pinfunction "VREF+_21") (pintype "unspecified"))
      (node (ref "U1") (pin "22") (pinfunction "VDDA_22") (pintype "unspecified"))
      (node (ref "U1") (pin "28") (pinfunction "VDD_4_28") (pintype "unspecified"))
      (node (ref "U1") (pin "50") (pinfunction "VDD_1_50") (pintype "unspecified"))
      (node (ref "U1") (pin "6") (pinfunction "VBAT_6") (pintype "unspecified"))
      (node (ref "U1") (pin "75") (pinfunction "VDD_2_75") (pintype "unspecified"))
      (node (ref "U4") (pin "2") (pinfunction "Vout_2") (pintype "unspecified"))
      (node (ref "U4") (pin "4") (pinfunction "Vout_4") (pintype "unspecified"))
      (node (ref "U9") (pin "100") (pinfunction "VDD_3_100") (pintype "unspecified"))
      (node (ref "U9") (pin "11") (pinfunction "VDD_5_11") (pintype "unspecified"))
      (node (ref "U9") (pin "21") (pinfunction "VREF+_21") (pintype "unspecified"))
      (node (ref "U9") (pin "22") (pinfunction "VDDA_22") (pintype "unspecified"))
      (node (ref "U9") (pin "28") (pinfunction "VDD_4_28") (pintype "unspecified"))
      (node (ref "U9") (pin "50") (pinfunction "VDD_1_50") (pintype "unspecified"))
      (node (ref "U9") (pin "6") (pinfunction "VBAT_6") (pintype "unspecified"))
      (node (ref "U9") (pin "75") (pinfunction "VDD_2_75") (pintype "unspecified"))
    )
    (net (code "121") (name "V5") (class "Default")
      (node (ref "C1") (pin "1") (pinfunction "1_1") (pintype "input"))
      (node (ref "C2") (pin "1") (pinfunction "1_1") (pintype "input"))
      (node (ref "C3") (pin "2") (pinfunction "2_2") (pintype "unspecified"))
      (node (ref "D1") (pin "1") (pinfunction "-_1") (pintype "unspecified"))
      (node (ref "D2") (pin "1") (pinfunction "-_1") (pintype "unspecified"))
      (node (ref "LED3") (pin "2") (pinfunction "+_2") (pintype "unspecified"))
      (node (ref "Q1") (pin "2") (pinfunction "S_2") (pintype "unspecified"))
      (node (ref "R11") (pin "2") (pinfunction "2_2") (pintype "input"))
      (node (ref "R12") (pin "1") (pinfunction "1_1") (pintype "input"))
      (node (ref "U11") (pin "5") (pinfunction "VCC_5") (pintype "unspecified"))
      (node (ref "U13") (pin "5") (pinfunction "VCC_5") (pintype "unspecified"))
      (node (ref "U2") (pin "37") (pinfunction "VCC_37") (pintype "passive"))
      (node (ref "U2") (pin "47") (pinfunction "BYTE_47") (pintype "unspecified"))
      (node (ref "U3") (pin "37") (pinfunction "VCC_37") (pintype "passive"))
      (node (ref "U3") (pin "47") (pinfunction "BYTE_47") (pintype "unspecified"))
      (node (ref "U4") (pin "3") (pinfunction "Vin_3") (pintype "unspecified"))
      (node (ref "U5") (pin "18") (pinfunction "VCC_18") (pintype "unspecified"))
      (node (ref "U5") (pin "31") (pinfunction "VCC_31") (pintype "unspecified"))
      (node (ref "U5") (pin "42") (pinfunction "VCC_42") (pintype "unspecified"))
      (node (ref "U5") (pin "7") (pinfunction "VCC_7") (pintype "unspecified"))
      (node (ref "U6") (pin "18") (pinfunction "VCC_18") (pintype "unspecified"))
      (node (ref "U6") (pin "31") (pinfunction "VCC_31") (pintype "unspecified"))
      (node (ref "U6") (pin "42") (pinfunction "VCC_42") (pintype "unspecified"))
      (node (ref "U6") (pin "7") (pinfunction "VCC_7") (pintype "unspecified"))
    )
    (net (code "122") (name "unconnected-(H1R-Pad10)") (class "Default")
      (node (ref "H1R") (pin "10") (pinfunction "10_10") (pintype "unspecified+no_connect"))
    )
    (net (code "123") (name "unconnected-(H2L-Pad1)") (class "Default")
      (node (ref "H2L") (pin "1") (pinfunction "1_1") (pintype "unspecified+no_connect"))
    )
    (net (code "124") (name "unconnected-(H3L-Pad1)") (class "Default")
      (node (ref "H3L") (pin "1") (pinfunction "1_1") (pintype "unspecified+no_connect"))
    )
    (net (code "125") (name "unconnected-(H3L-Pad2)") (class "Default")
      (node (ref "H3L") (pin "2") (pinfunction "2_2") (pintype "unspecified+no_connect"))
    )
    (net (code "126") (name "unconnected-(H4L-Pad1)") (class "Default")
      (node (ref "H4L") (pin "1") (pinfunction "1_1") (pintype "unspecified+no_connect"))
    )
    (net (code "127") (name "unconnected-(H4L-Pad2)") (class "Default")
      (node (ref "H4L") (pin "2") (pinfunction "2_2") (pintype "unspecified+no_connect"))
    )
    (net (code "128") (name "unconnected-(H4L-Pad20)") (class "Default")
      (node (ref "H4L") (pin "20") (pinfunction "20_20") (pintype "unspecified+no_connect"))
    )
    (net (code "129") (name "unconnected-(H5L-Pad1)") (class "Default")
      (node (ref "H5L") (pin "1") (pinfunction "1_1") (pintype "unspecified+no_connect"))
    )
    (net (code "130") (name "unconnected-(H5L-Pad2)") (class "Default")
      (node (ref "H5L") (pin "2") (pinfunction "2_2") (pintype "unspecified+no_connect"))
    )
    (net (code "131") (name "unconnected-(H5R-Pad2)") (class "Default")
      (node (ref "H5R") (pin "2") (pinfunction "2_2") (pintype "unspecified+no_connect"))
    )
    (net (code "132") (name "unconnected-(H7L-Pad1)") (class "Default")
      (node (ref "H7L") (pin "1") (pinfunction "1_1") (pintype "unspecified+no_connect"))
    )
    (net (code "133") (name "unconnected-(H7L-Pad2)") (class "Default")
      (node (ref "H7L") (pin "2") (pinfunction "2_2") (pintype "unspecified+no_connect"))
    )
    (net (code "134") (name "unconnected-(U1-NC-Pad73)") (class "Default")
      (node (ref "U1") (pin "73") (pinfunction "NC_73") (pintype "unspecified"))
    )
    (net (code "135") (name "unconnected-(U1-PA15-Pad77)") (class "Default")
      (node (ref "U1") (pin "77") (pinfunction "PA15_77") (pintype "unspecified"))
    )
    (net (code "136") (name "unconnected-(U1-PB1-Pad36)") (class "Default")
      (node (ref "U1") (pin "36") (pinfunction "PB1_36") (pintype "unspecified"))
    )
    (net (code "137") (name "unconnected-(U2-NC-Pad10)") (class "Default")
      (node (ref "U2") (pin "10") (pinfunction "NC_10") (pintype "unspecified+no_connect"))
    )
    (net (code "138") (name "unconnected-(U2-NC-Pad13)") (class "Default")
      (node (ref "U2") (pin "13") (pinfunction "NC_13") (pintype "unspecified+no_connect"))
    )
    (net (code "139") (name "unconnected-(U2-NC-Pad14)") (class "Default")
      (node (ref "U2") (pin "14") (pinfunction "NC_14") (pintype "unspecified+no_connect"))
    )
    (net (code "140") (name "unconnected-(U2-RB-Pad15)") (class "Default")
      (node (ref "U2") (pin "15") (pinfunction "RB_15") (pintype "unspecified+no_connect"))
    )
    (net (code "141") (name "unconnected-(U3-NC-Pad10)") (class "Default")
      (node (ref "U3") (pin "10") (pinfunction "NC_10") (pintype "unspecified+no_connect"))
    )
    (net (code "142") (name "unconnected-(U3-NC-Pad13)") (class "Default")
      (node (ref "U3") (pin "13") (pinfunction "NC_13") (pintype "unspecified+no_connect"))
    )
    (net (code "143") (name "unconnected-(U3-NC-Pad14)") (class "Default")
      (node (ref "U3") (pin "14") (pinfunction "NC_14") (pintype "unspecified+no_connect"))
    )
    (net (code "144") (name "unconnected-(U3-RB-Pad15)") (class "Default")
      (node (ref "U3") (pin "15") (pinfunction "RB_15") (pintype "unspecified+no_connect"))
    )
    (net (code "145") (name "unconnected-(U9-NC-Pad73)") (class "Default")
      (node (ref "U9") (pin "73") (pinfunction "NC_73") (pintype "unspecified+no_connect"))
    )
    (net (code "146") (name "unconnected-(U9-PA15-Pad77)") (class "Default")
      (node (ref "U9") (pin "77") (pinfunction "PA15_77") (pintype "unspecified+no_connect"))
    )
    (net (code "147") (name "unconnected-(U9-PB1-Pad36)") (class "Default")
      (node (ref "U9") (pin "36") (pinfunction "PB1_36") (pintype "unspecified+no_connect"))
    )
    (net (code "148") (name "unconnected-(U13-NC-Pad1)") (class "Default")
      (node (ref "U13") (pin "1") (pinfunction "NC_1") (pintype "unspecified+no_connect"))
    )
    (net (code "149") (name "unconnected-(USBC1-SBU1-PadA8)") (class "Default")
      (node (ref "USBC1") (pin "A8") (pinfunction "SBU1_A8") (pintype "unspecified+no_connect"))
    )
    (net (code "150") (name "unconnected-(USBC1-SBU2-PadB8)") (class "Default")
      (node (ref "USBC1") (pin "B8") (pinfunction "SBU2_B8") (pintype "unspecified+no_connect"))
    )
    (net (code "151") (name "unconnected-(USBC2-SUB1-PadA8)") (class "Default")
      (node (ref "USBC2") (pin "A8") (pinfunction "SUB1_A8") (pintype "unspecified+no_connect"))
    )
    (net (code "152") (name "unconnected-(USBC2-SUB2-PadB8)") (class "Default")
      (node (ref "USBC2") (pin "B8") (pinfunction "SUB2_B8") (pintype "unspecified+no_connect"))
    )
  )
)
